# M1705Beco.net
KiCad netlist of a schematic drawn in EAGLE
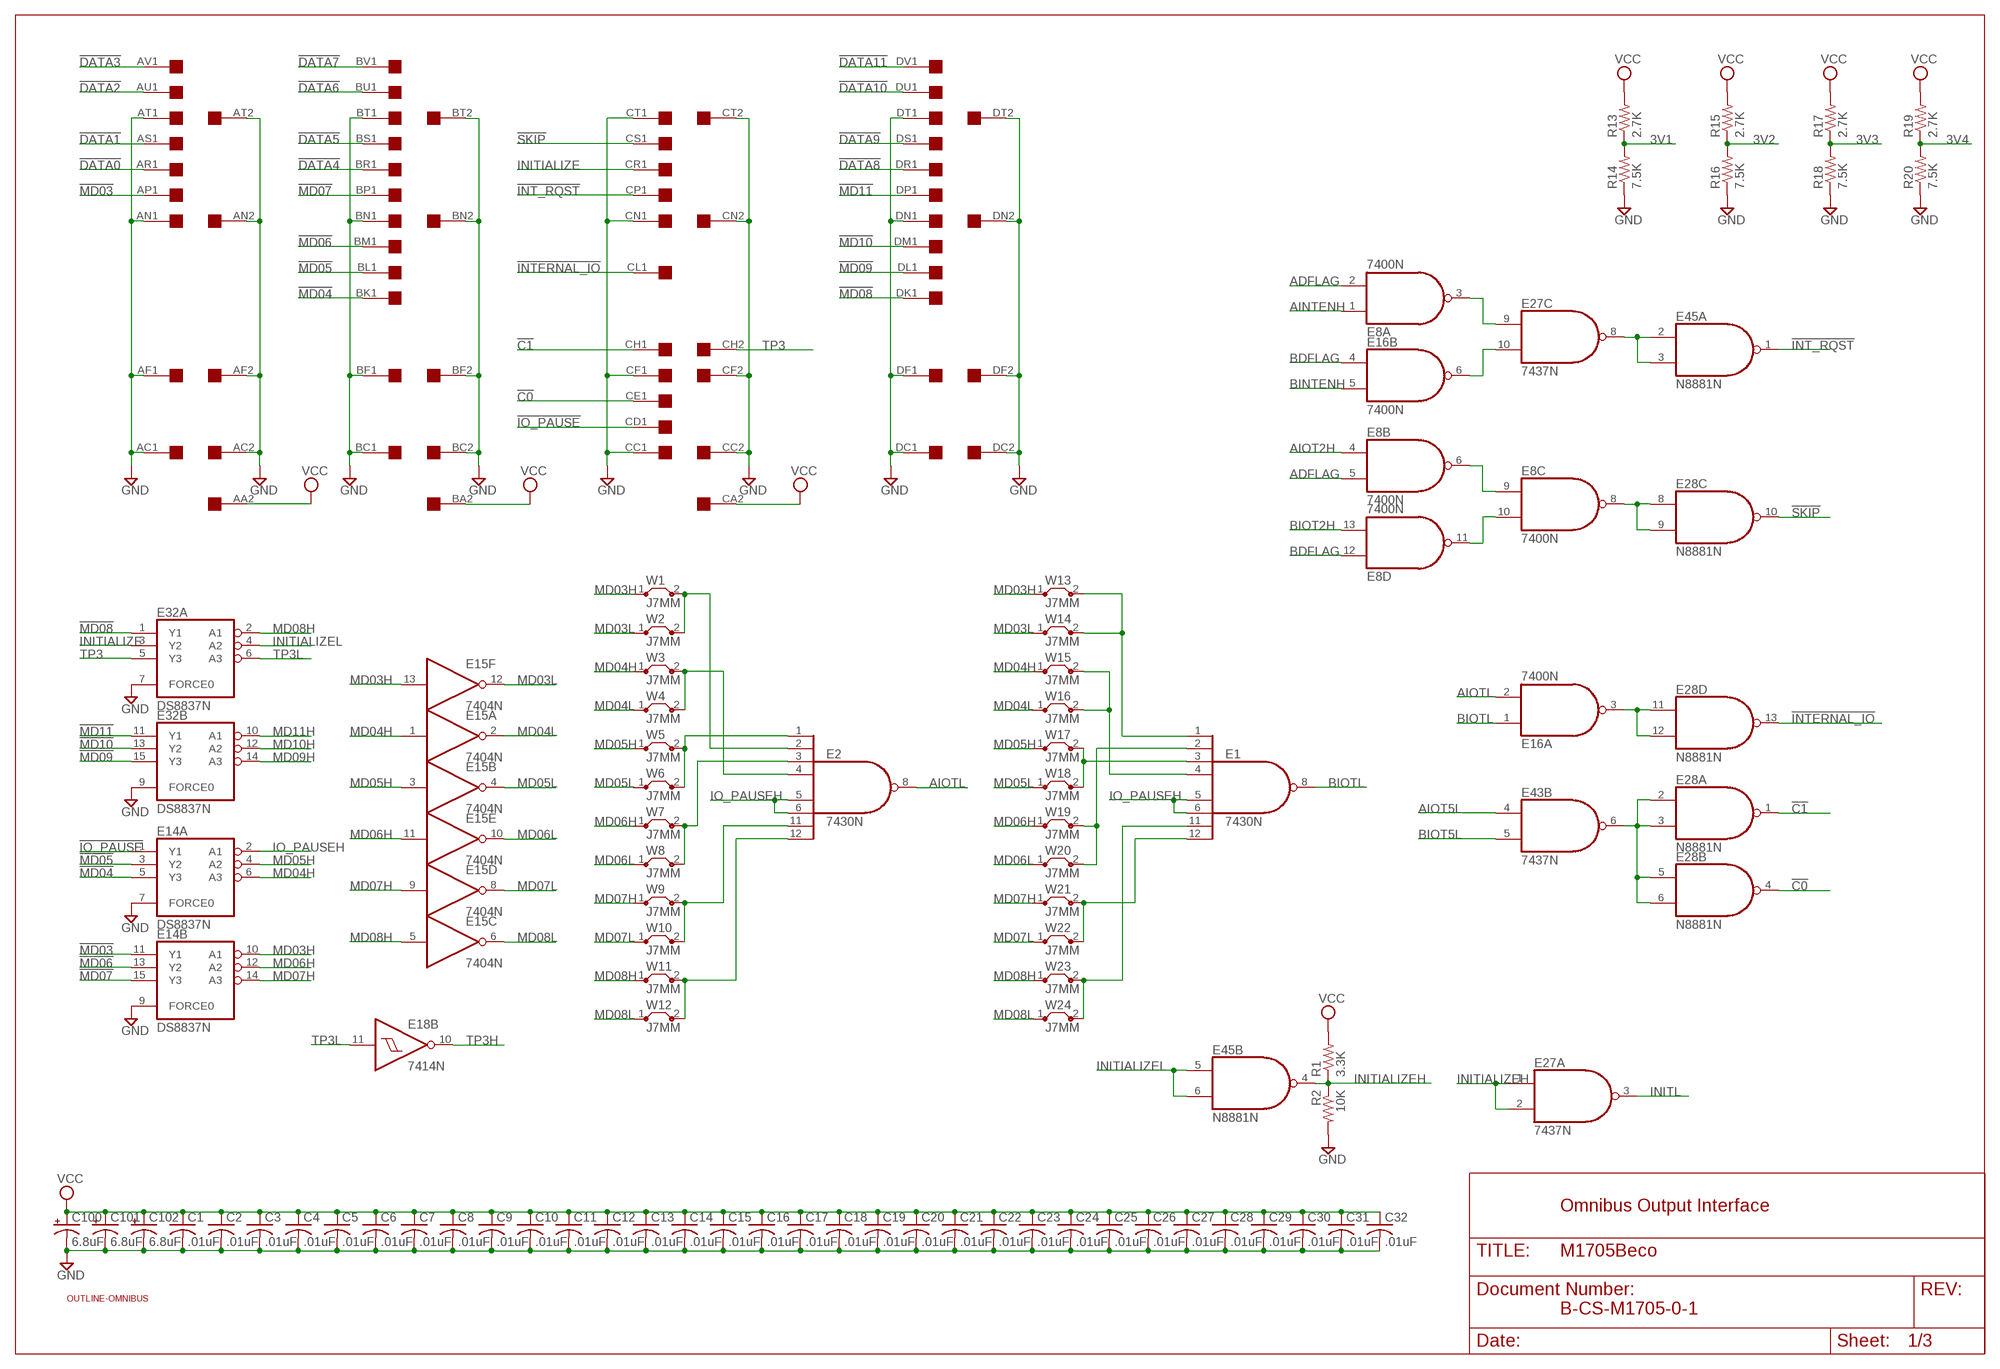
[diagram p0: schematic, sheet 1]
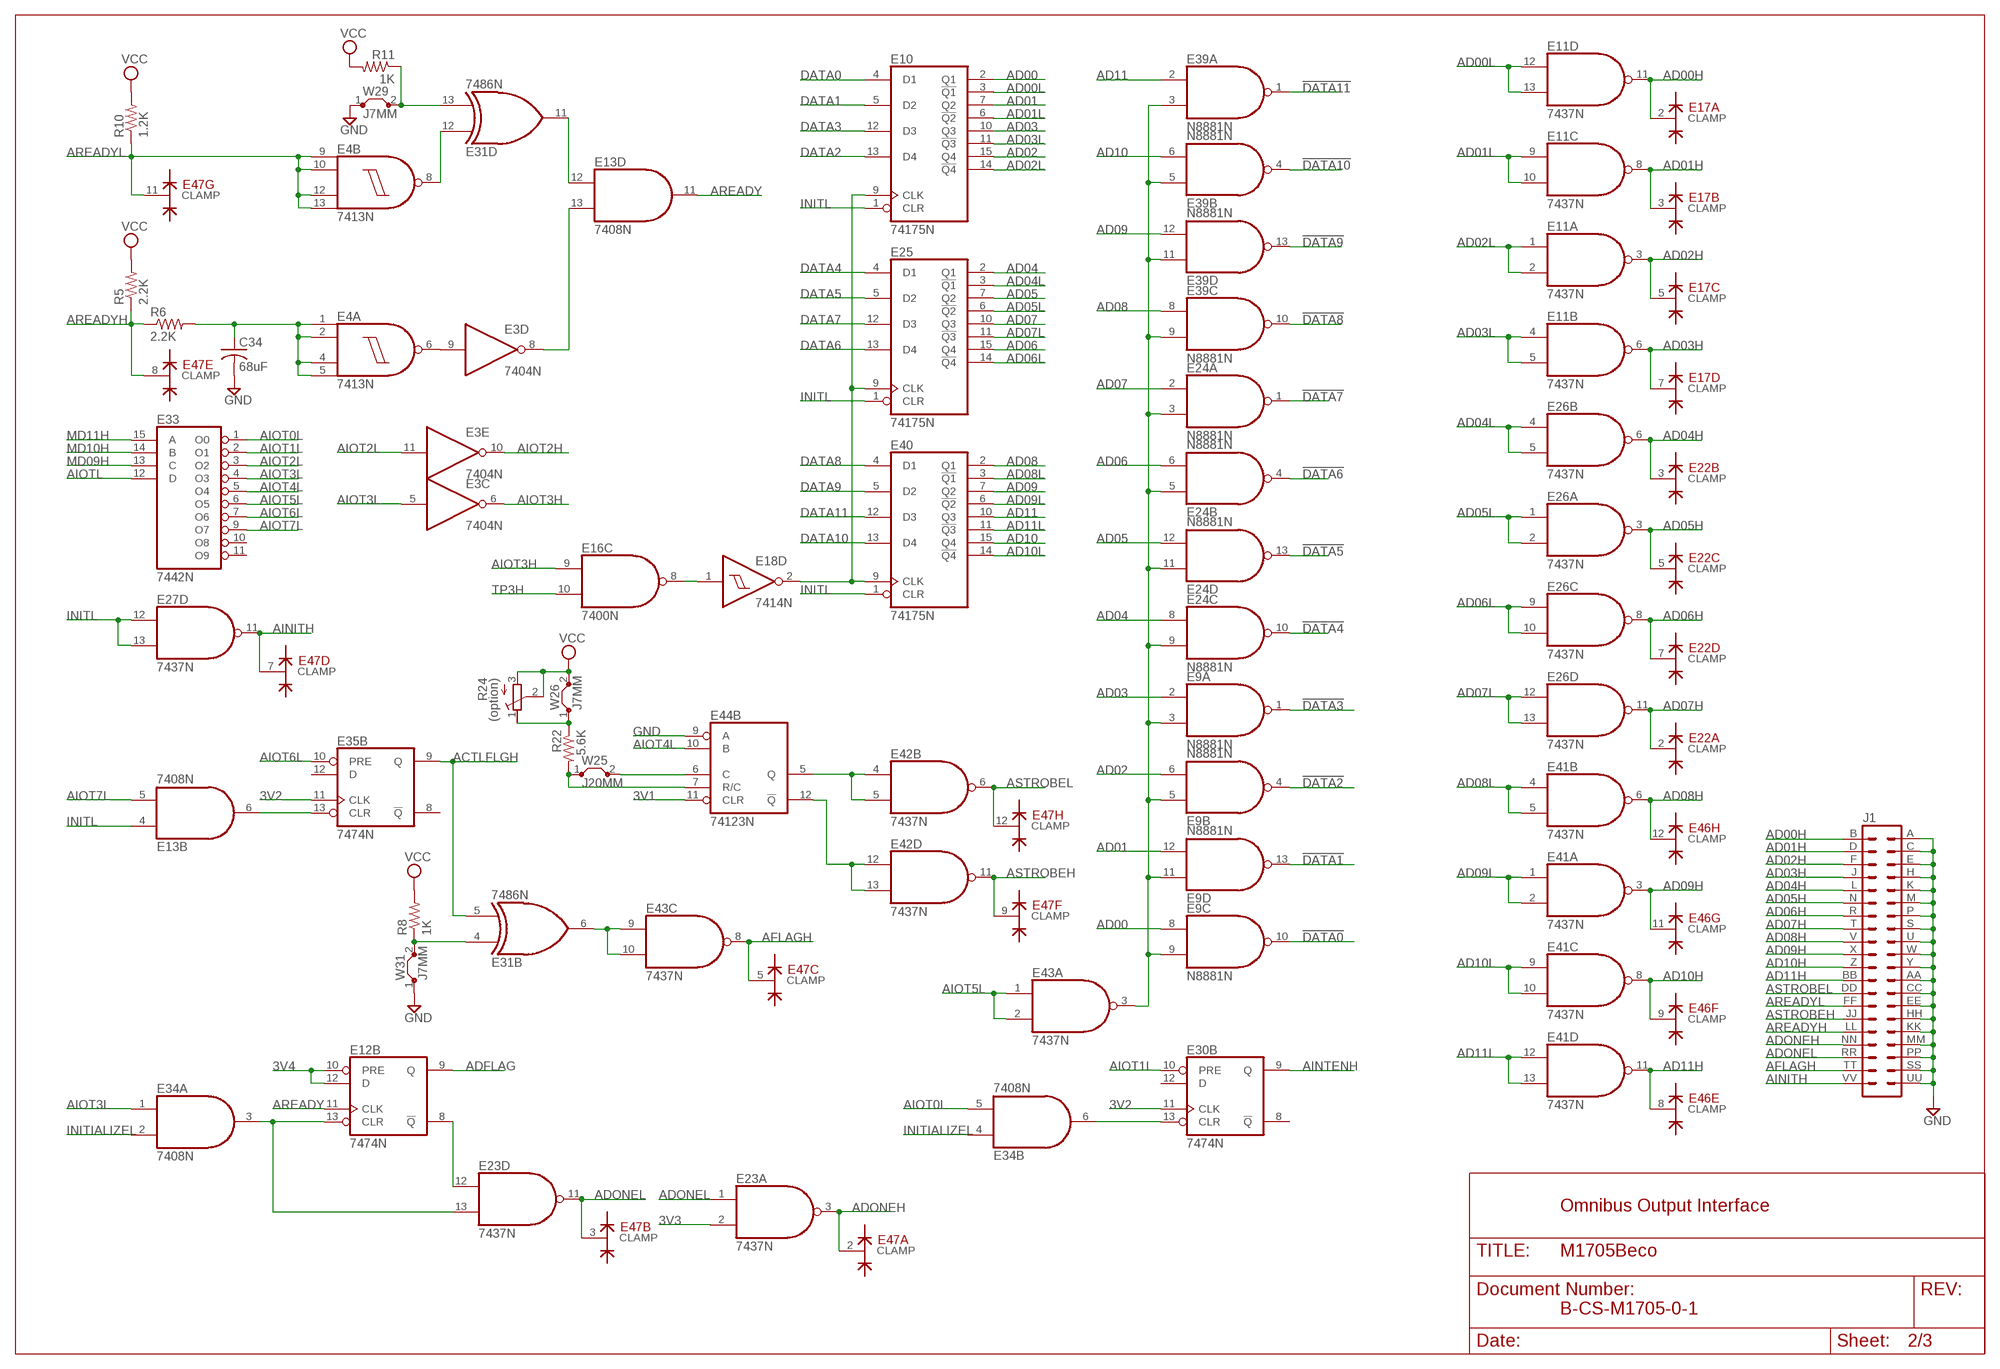
[diagram p1: schematic, sheet 2]
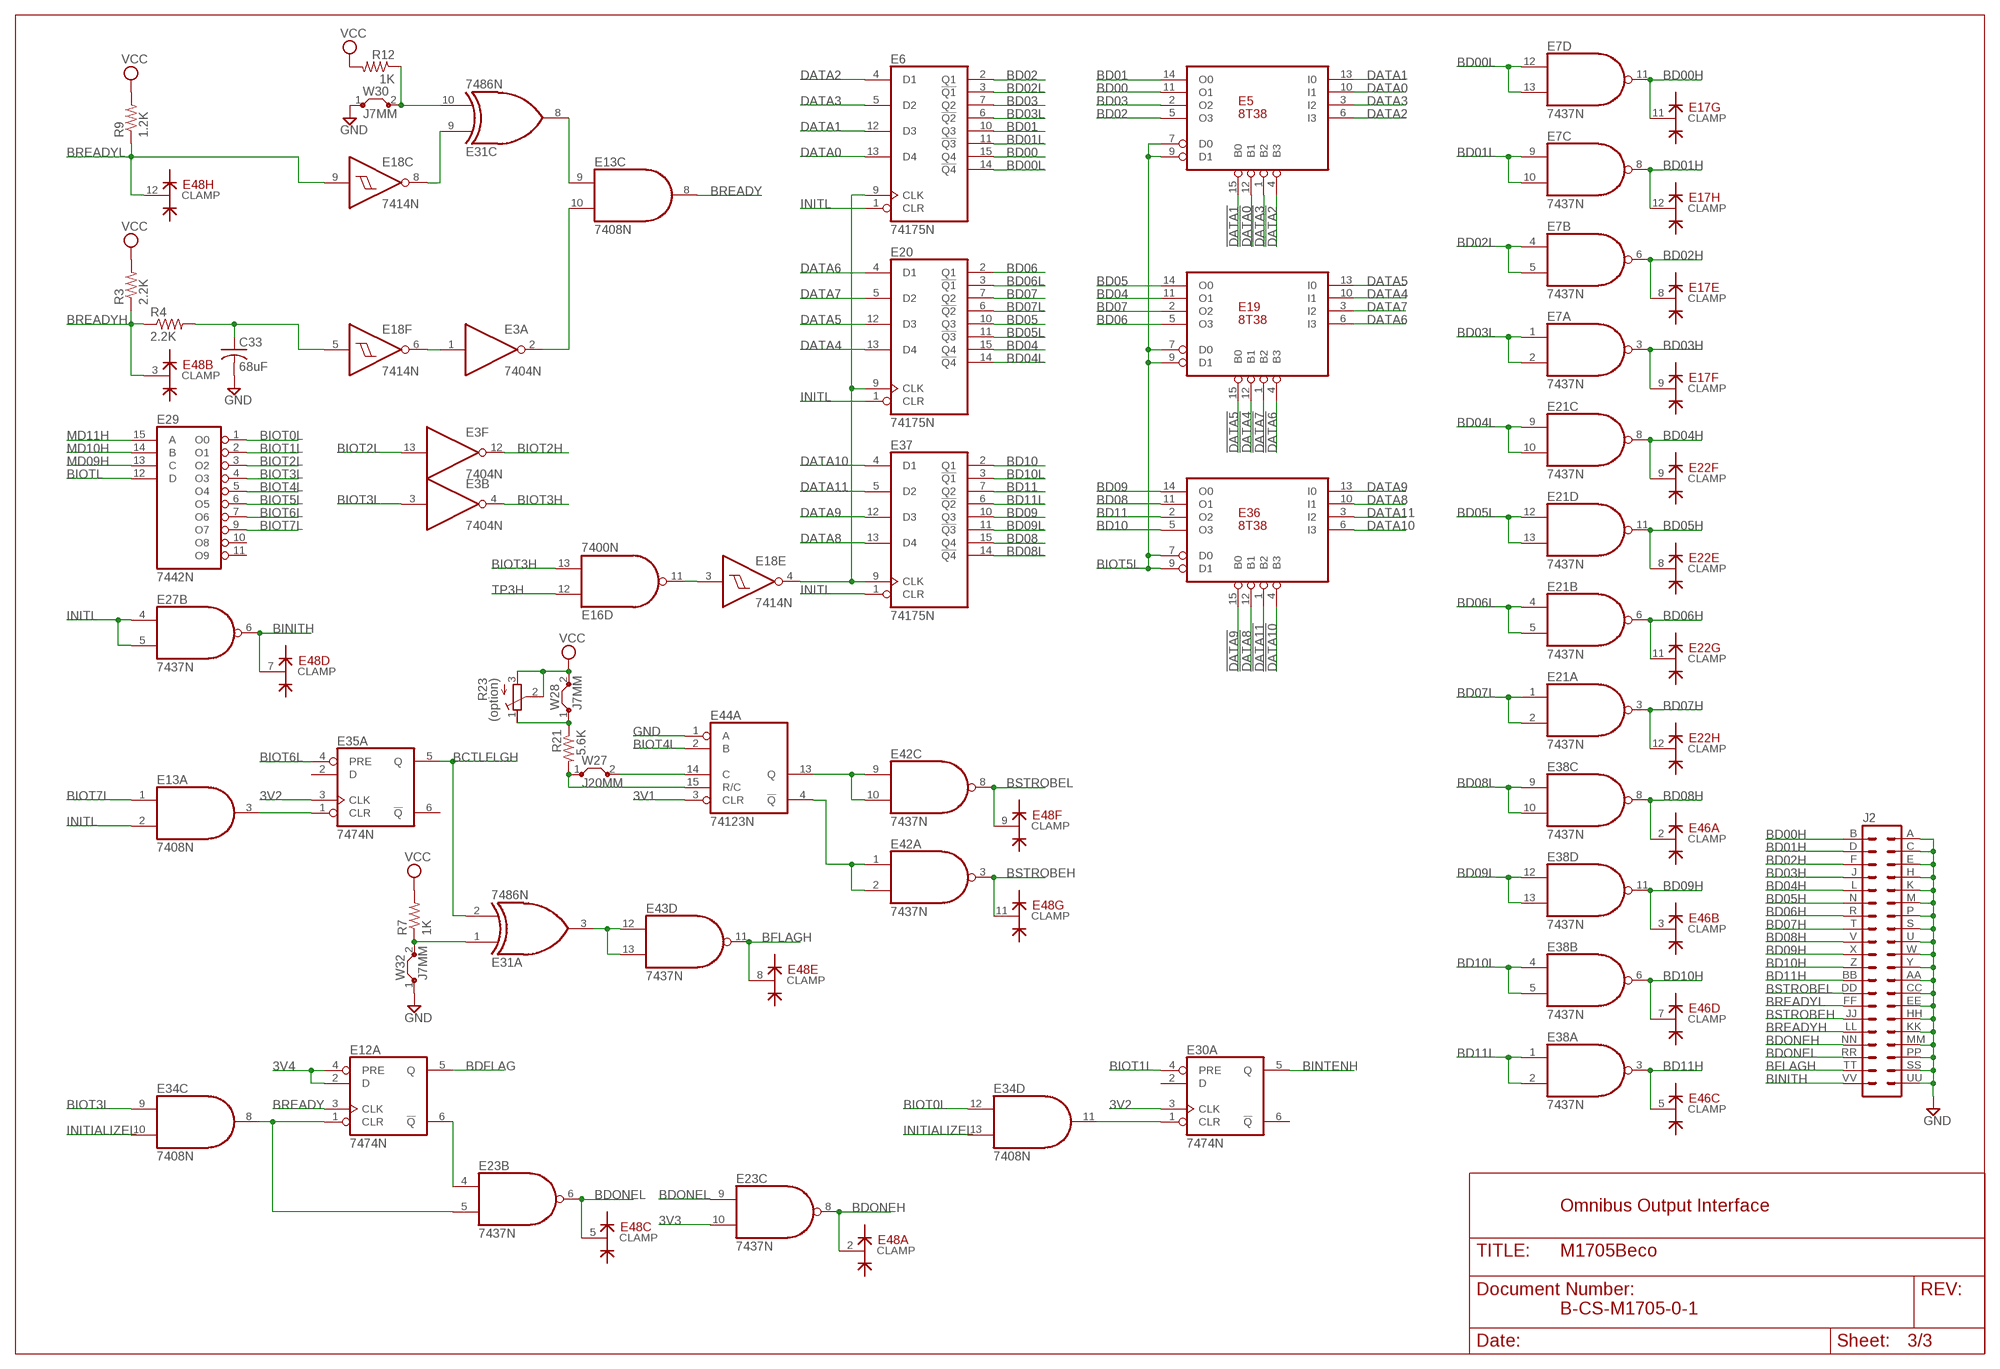
[diagram p2: schematic, sheet 3]

(export (version "E")
  (design (tool "Eeschema 10.0.6"))
  (components
    (comp (ref "C33")
      (value "68uF")
      (footprint "eagle-import:C102-043X133")
      (libsource (lib "eagle-import") (part "C-US102-043X133"))
    )
    (comp (ref "E3")
      (value "7404N")
      (footprint "eagle-import:DIL14")
      (libsource (lib "eagle-import") (part "7404N"))
    )
    (comp (ref "E5")
      (value "8T38")
      (footprint "eagle-import:DIL16")
      (libsource (lib "eagle-import") (part "DS8641N"))
    )
    (comp (ref "E6")
      (value "74175N")
      (footprint "eagle-import:DIL16")
      (libsource (lib "eagle-import") (part "74175N"))
    )
    (comp (ref "E7")
      (value "7437N")
      (footprint "eagle-import:DIL14")
      (libsource (lib "eagle-import") (part "7437N"))
    )
    (comp (ref "E12")
      (value "7474N")
      (footprint "eagle-import:DIL14")
      (libsource (lib "eagle-import") (part "7474NS"))
    )
    (comp (ref "E13")
      (value "7408N")
      (footprint "eagle-import:DIL14")
      (libsource (lib "eagle-import") (part "7408NLS"))
    )
    (comp (ref "E16")
      (value "7400N")
      (footprint "eagle-import:DIL14")
      (libsource (lib "eagle-import") (part "7400N"))
    )
    (comp (ref "E17")
      (value "DEC2501")
      (footprint "eagle-import:DIL14")
      (libsource (lib "eagle-import") (part "DEC2501"))
    )
    (comp (ref "E18")
      (value "7414N")
      (footprint "eagle-import:DIL14")
      (libsource (lib "eagle-import") (part "7414N"))
    )
    (comp (ref "E19")
      (value "8T38")
      (footprint "eagle-import:DIL16")
      (libsource (lib "eagle-import") (part "DS8641N"))
    )
    (comp (ref "E20")
      (value "74175N")
      (footprint "eagle-import:DIL16")
      (libsource (lib "eagle-import") (part "74175N"))
    )
    (comp (ref "E21")
      (value "7437N")
      (footprint "eagle-import:DIL14")
      (libsource (lib "eagle-import") (part "7437N"))
    )
    (comp (ref "E22")
      (value "DEC2501")
      (footprint "eagle-import:DIL14")
      (libsource (lib "eagle-import") (part "DEC2501"))
    )
    (comp (ref "E23")
      (value "7437N")
      (footprint "eagle-import:DIL14")
      (libsource (lib "eagle-import") (part "7437N"))
    )
    (comp (ref "E27")
      (value "7437N")
      (footprint "eagle-import:DIL14")
      (libsource (lib "eagle-import") (part "7437N"))
    )
    (comp (ref "E29")
      (value "7442N")
      (footprint "eagle-import:DIL16")
      (libsource (lib "eagle-import") (part "7442NLS"))
    )
    (comp (ref "E30")
      (value "7474N")
      (footprint "eagle-import:DIL14")
      (libsource (lib "eagle-import") (part "7474NS"))
    )
    (comp (ref "E31")
      (value "7486N")
      (footprint "eagle-import:DIL14")
      (libsource (lib "eagle-import") (part "7486N"))
    )
    (comp (ref "E34")
      (value "7408N")
      (footprint "eagle-import:DIL14")
      (libsource (lib "eagle-import") (part "7408NLS"))
    )
    (comp (ref "E35")
      (value "7474N")
      (footprint "eagle-import:DIL14")
      (libsource (lib "eagle-import") (part "7474NS"))
    )
    (comp (ref "E36")
      (value "8T38")
      (footprint "eagle-import:DIL16")
      (libsource (lib "eagle-import") (part "DS8641N"))
    )
    (comp (ref "E37")
      (value "74175N")
      (footprint "eagle-import:DIL16")
      (libsource (lib "eagle-import") (part "74175N"))
    )
    (comp (ref "E38")
      (value "7437N")
      (footprint "eagle-import:DIL14")
      (libsource (lib "eagle-import") (part "7437N"))
    )
    (comp (ref "E42")
      (value "7437N")
      (footprint "eagle-import:DIL14")
      (libsource (lib "eagle-import") (part "7437N"))
    )
    (comp (ref "E43")
      (value "7437N")
      (footprint "eagle-import:DIL14")
      (libsource (lib "eagle-import") (part "7437N"))
    )
    (comp (ref "E44")
      (value "74123N")
      (footprint "eagle-import:DIL16")
      (libsource (lib "eagle-import") (part "74123N"))
    )
    (comp (ref "E46")
      (value "DEC2501")
      (footprint "eagle-import:DIL14")
      (libsource (lib "eagle-import") (part "DEC2501"))
    )
    (comp (ref "E48")
      (value "DEC2501")
      (footprint "eagle-import:DIL14")
      (libsource (lib "eagle-import") (part "DEC2501"))
    )
    (comp (ref "J2")
      (value "DEC40PINH")
      (footprint "eagle-import:DEC40PINH")
      (libsource (lib "eagle-import") (part "DEC40PINH"))
    )
    (comp (ref "R3")
      (value "2.2K")
      (footprint "eagle-import:0207_10")
      (libsource (lib "eagle-import") (part "R-US_0207/10"))
    )
    (comp (ref "R4")
      (value "2.2K")
      (footprint "eagle-import:0207_10")
      (libsource (lib "eagle-import") (part "R-US_0207/10"))
    )
    (comp (ref "R7")
      (value "1K")
      (footprint "eagle-import:0207_10")
      (libsource (lib "eagle-import") (part "R-US_0207/10"))
    )
    (comp (ref "R9")
      (value "1.2K")
      (footprint "eagle-import:0207_10")
      (libsource (lib "eagle-import") (part "R-US_0207/10"))
    )
    (comp (ref "R12")
      (value "1K")
      (footprint "eagle-import:0207_10")
      (libsource (lib "eagle-import") (part "R-US_0207/10"))
    )
    (comp (ref "R21")
      (value "5.6K")
      (footprint "eagle-import:0207_10")
      (libsource (lib "eagle-import") (part "R-US_0207/10"))
    )
    (comp (ref "R23")
      (value "(option)")
      (footprint "eagle-import:3006Y")
      (libsource (lib "eagle-import") (part "275P"))
    )
    (comp (ref "W27")
      (value "J20MM")
      (footprint "eagle-import:20")
      (libsource (lib "eagle-import") (part "J20MM"))
    )
    (comp (ref "W28")
      (value "J7MM")
      (footprint "eagle-import:07")
      (libsource (lib "eagle-import") (part "J7MM"))
    )
    (comp (ref "W30")
      (value "J7MM")
      (footprint "eagle-import:07")
      (libsource (lib "eagle-import") (part "J7MM"))
    )
    (comp (ref "W32")
      (value "J7MM")
      (footprint "eagle-import:07")
      (libsource (lib "eagle-import") (part "J7MM"))
    )
    (comp (ref "C1")
      (value ".01uF")
      (footprint "eagle-import:C075-032X103")
      (libsource (lib "eagle-import") (part "C-US075-032X103"))
    )
    (comp (ref "C2")
      (value ".01uF")
      (footprint "eagle-import:C075-032X103")
      (libsource (lib "eagle-import") (part "C-US075-032X103"))
    )
    (comp (ref "C3")
      (value ".01uF")
      (footprint "eagle-import:C075-032X103")
      (libsource (lib "eagle-import") (part "C-US075-032X103"))
    )
    (comp (ref "C4")
      (value ".01uF")
      (footprint "eagle-import:C075-032X103")
      (libsource (lib "eagle-import") (part "C-US075-032X103"))
    )
    (comp (ref "C5")
      (value ".01uF")
      (footprint "eagle-import:C075-032X103")
      (libsource (lib "eagle-import") (part "C-US075-032X103"))
    )
    (comp (ref "C6")
      (value ".01uF")
      (footprint "eagle-import:C075-032X103")
      (libsource (lib "eagle-import") (part "C-US075-032X103"))
    )
    (comp (ref "C7")
      (value ".01uF")
      (footprint "eagle-import:C075-032X103")
      (libsource (lib "eagle-import") (part "C-US075-032X103"))
    )
    (comp (ref "C8")
      (value ".01uF")
      (footprint "eagle-import:C075-032X103")
      (libsource (lib "eagle-import") (part "C-US075-032X103"))
    )
    (comp (ref "C9")
      (value ".01uF")
      (footprint "eagle-import:C075-032X103")
      (libsource (lib "eagle-import") (part "C-US075-032X103"))
    )
    (comp (ref "C10")
      (value ".01uF")
      (footprint "eagle-import:C075-032X103")
      (libsource (lib "eagle-import") (part "C-US075-032X103"))
    )
    (comp (ref "C11")
      (value ".01uF")
      (footprint "eagle-import:C075-032X103")
      (libsource (lib "eagle-import") (part "C-US075-032X103"))
    )
    (comp (ref "C12")
      (value ".01uF")
      (footprint "eagle-import:C075-032X103")
      (libsource (lib "eagle-import") (part "C-US075-032X103"))
    )
    (comp (ref "C13")
      (value ".01uF")
      (footprint "eagle-import:C075-032X103")
      (libsource (lib "eagle-import") (part "C-US075-032X103"))
    )
    (comp (ref "C14")
      (value ".01uF")
      (footprint "eagle-import:C075-032X103")
      (libsource (lib "eagle-import") (part "C-US075-032X103"))
    )
    (comp (ref "C15")
      (value ".01uF")
      (footprint "eagle-import:C075-032X103")
      (libsource (lib "eagle-import") (part "C-US075-032X103"))
    )
    (comp (ref "C16")
      (value ".01uF")
      (footprint "eagle-import:C075-032X103")
      (libsource (lib "eagle-import") (part "C-US075-032X103"))
    )
    (comp (ref "C17")
      (value ".01uF")
      (footprint "eagle-import:C075-032X103")
      (libsource (lib "eagle-import") (part "C-US075-032X103"))
    )
    (comp (ref "C18")
      (value ".01uF")
      (footprint "eagle-import:C075-032X103")
      (libsource (lib "eagle-import") (part "C-US075-032X103"))
    )
    (comp (ref "C19")
      (value ".01uF")
      (footprint "eagle-import:C075-032X103")
      (libsource (lib "eagle-import") (part "C-US075-032X103"))
    )
    (comp (ref "C20")
      (value ".01uF")
      (footprint "eagle-import:C075-032X103")
      (libsource (lib "eagle-import") (part "C-US075-032X103"))
    )
    (comp (ref "C21")
      (value ".01uF")
      (footprint "eagle-import:C075-032X103")
      (libsource (lib "eagle-import") (part "C-US075-032X103"))
    )
    (comp (ref "C22")
      (value ".01uF")
      (footprint "eagle-import:C075-032X103")
      (libsource (lib "eagle-import") (part "C-US075-032X103"))
    )
    (comp (ref "C23")
      (value ".01uF")
      (footprint "eagle-import:C075-032X103")
      (libsource (lib "eagle-import") (part "C-US075-032X103"))
    )
    (comp (ref "C24")
      (value ".01uF")
      (footprint "eagle-import:C075-032X103")
      (libsource (lib "eagle-import") (part "C-US075-032X103"))
    )
    (comp (ref "C25")
      (value ".01uF")
      (footprint "eagle-import:C075-032X103")
      (libsource (lib "eagle-import") (part "C-US075-032X103"))
    )
    (comp (ref "C26")
      (value ".01uF")
      (footprint "eagle-import:C075-032X103")
      (libsource (lib "eagle-import") (part "C-US075-032X103"))
    )
    (comp (ref "C27")
      (value ".01uF")
      (footprint "eagle-import:C075-032X103")
      (libsource (lib "eagle-import") (part "C-US075-032X103"))
    )
    (comp (ref "C28")
      (value ".01uF")
      (footprint "eagle-import:C075-032X103")
      (libsource (lib "eagle-import") (part "C-US075-032X103"))
    )
    (comp (ref "C29")
      (value ".01uF")
      (footprint "eagle-import:C075-032X103")
      (libsource (lib "eagle-import") (part "C-US075-032X103"))
    )
    (comp (ref "C30")
      (value ".01uF")
      (footprint "eagle-import:C075-032X103")
      (libsource (lib "eagle-import") (part "C-US075-032X103"))
    )
    (comp (ref "C31")
      (value ".01uF")
      (footprint "eagle-import:C075-032X103")
      (libsource (lib "eagle-import") (part "C-US075-032X103"))
    )
    (comp (ref "C32")
      (value ".01uF")
      (footprint "eagle-import:C075-032X103")
      (libsource (lib "eagle-import") (part "C-US075-032X103"))
    )
    (comp (ref "C100")
      (value "6.8uF")
      (footprint "eagle-import:E12-8")
      (libsource (lib "eagle-import") (part "CPOL-USE20-8AXIAL"))
    )
    (comp (ref "C101")
      (value "6.8uF")
      (footprint "eagle-import:E12-8")
      (libsource (lib "eagle-import") (part "CPOL-USE20-8AXIAL"))
    )
    (comp (ref "C102")
      (value "6.8uF")
      (footprint "eagle-import:E12-8")
      (libsource (lib "eagle-import") (part "CPOL-USE20-8AXIAL"))
    )
    (comp (ref "E1")
      (value "7430N")
      (footprint "eagle-import:DIL14")
      (libsource (lib "eagle-import") (part "7430N"))
    )
    (comp (ref "E2")
      (value "7430N")
      (footprint "eagle-import:DIL14")
      (libsource (lib "eagle-import") (part "7430N"))
    )
    (comp (ref "E8")
      (value "7400N")
      (footprint "eagle-import:DIL14")
      (libsource (lib "eagle-import") (part "7400N"))
    )
    (comp (ref "E14")
      (value "DS8837N")
      (footprint "eagle-import:DIL16")
      (libsource (lib "eagle-import") (part "DS8837N"))
    )
    (comp (ref "E15")
      (value "7404N")
      (footprint "eagle-import:DIL14")
      (libsource (lib "eagle-import") (part "7404N"))
    )
    (comp (ref "E28")
      (value "N8881N")
      (footprint "eagle-import:DIL14")
      (libsource (lib "eagle-import") (part "N8881N"))
    )
    (comp (ref "E32")
      (value "DS8837N")
      (footprint "eagle-import:DIL16")
      (libsource (lib "eagle-import") (part "DS8837N"))
    )
    (comp (ref "E45")
      (value "N8881N")
      (footprint "eagle-import:DIL14")
      (libsource (lib "eagle-import") (part "N8881N"))
    )
    (comp (ref "R1")
      (value "3.3K")
      (footprint "eagle-import:0207_10")
      (libsource (lib "eagle-import") (part "R-US_0207/10"))
    )
    (comp (ref "R2")
      (value "10K")
      (footprint "eagle-import:0207_10")
      (libsource (lib "eagle-import") (part "R-US_0207/10"))
    )
    (comp (ref "R13")
      (value "2.7K")
      (footprint "eagle-import:0207_10")
      (libsource (lib "eagle-import") (part "R-US_0207/10"))
    )
    (comp (ref "R14")
      (value "7.5K")
      (footprint "eagle-import:0207_10")
      (libsource (lib "eagle-import") (part "R-US_0207/10"))
    )
    (comp (ref "R15")
      (value "2.7K")
      (footprint "eagle-import:0207_10")
      (libsource (lib "eagle-import") (part "R-US_0207/10"))
    )
    (comp (ref "R16")
      (value "7.5K")
      (footprint "eagle-import:0207_10")
      (libsource (lib "eagle-import") (part "R-US_0207/10"))
    )
    (comp (ref "R17")
      (value "2.7K")
      (footprint "eagle-import:0207_10")
      (libsource (lib "eagle-import") (part "R-US_0207/10"))
    )
    (comp (ref "R18")
      (value "7.5K")
      (footprint "eagle-import:0207_10")
      (libsource (lib "eagle-import") (part "R-US_0207/10"))
    )
    (comp (ref "R19")
      (value "2.7K")
      (footprint "eagle-import:0207_10")
      (libsource (lib "eagle-import") (part "R-US_0207/10"))
    )
    (comp (ref "R20")
      (value "7.5K")
      (footprint "eagle-import:0207_10")
      (libsource (lib "eagle-import") (part "R-US_0207/10"))
    )
    (comp (ref "U$2")
      (value "QUAD")
      (footprint "eagle-import:EDGE-CON8")
      (libsource (lib "eagle-import") (part "QUAD"))
    )
    (comp (ref "U$4")
      (value "OUTLINE-OMNIBUS")
      (footprint "eagle-import:OMNIBUS")
      (libsource (lib "eagle-import") (part "OUTLINE-OMNIBUS"))
    )
    (comp (ref "W1")
      (value "J7MM")
      (footprint "eagle-import:07")
      (libsource (lib "eagle-import") (part "J7MM"))
    )
    (comp (ref "W2")
      (value "J7MM")
      (footprint "eagle-import:07")
      (libsource (lib "eagle-import") (part "J7MM"))
    )
    (comp (ref "W3")
      (value "J7MM")
      (footprint "eagle-import:07")
      (libsource (lib "eagle-import") (part "J7MM"))
    )
    (comp (ref "W4")
      (value "J7MM")
      (footprint "eagle-import:07")
      (libsource (lib "eagle-import") (part "J7MM"))
    )
    (comp (ref "W5")
      (value "J7MM")
      (footprint "eagle-import:07")
      (libsource (lib "eagle-import") (part "J7MM"))
    )
    (comp (ref "W6")
      (value "J7MM")
      (footprint "eagle-import:07")
      (libsource (lib "eagle-import") (part "J7MM"))
    )
    (comp (ref "W7")
      (value "J7MM")
      (footprint "eagle-import:07")
      (libsource (lib "eagle-import") (part "J7MM"))
    )
    (comp (ref "W8")
      (value "J7MM")
      (footprint "eagle-import:07")
      (libsource (lib "eagle-import") (part "J7MM"))
    )
    (comp (ref "W9")
      (value "J7MM")
      (footprint "eagle-import:07")
      (libsource (lib "eagle-import") (part "J7MM"))
    )
    (comp (ref "W10")
      (value "J7MM")
      (footprint "eagle-import:07")
      (libsource (lib "eagle-import") (part "J7MM"))
    )
    (comp (ref "W11")
      (value "J7MM")
      (footprint "eagle-import:07")
      (libsource (lib "eagle-import") (part "J7MM"))
    )
    (comp (ref "W12")
      (value "J7MM")
      (footprint "eagle-import:07")
      (libsource (lib "eagle-import") (part "J7MM"))
    )
    (comp (ref "W13")
      (value "J7MM")
      (footprint "eagle-import:07")
      (libsource (lib "eagle-import") (part "J7MM"))
    )
    (comp (ref "W14")
      (value "J7MM")
      (footprint "eagle-import:07")
      (libsource (lib "eagle-import") (part "J7MM"))
    )
    (comp (ref "W15")
      (value "J7MM")
      (footprint "eagle-import:07")
      (libsource (lib "eagle-import") (part "J7MM"))
    )
    (comp (ref "W16")
      (value "J7MM")
      (footprint "eagle-import:07")
      (libsource (lib "eagle-import") (part "J7MM"))
    )
    (comp (ref "W17")
      (value "J7MM")
      (footprint "eagle-import:07")
      (libsource (lib "eagle-import") (part "J7MM"))
    )
    (comp (ref "W18")
      (value "J7MM")
      (footprint "eagle-import:07")
      (libsource (lib "eagle-import") (part "J7MM"))
    )
    (comp (ref "W19")
      (value "J7MM")
      (footprint "eagle-import:07")
      (libsource (lib "eagle-import") (part "J7MM"))
    )
    (comp (ref "W20")
      (value "J7MM")
      (footprint "eagle-import:07")
      (libsource (lib "eagle-import") (part "J7MM"))
    )
    (comp (ref "W21")
      (value "J7MM")
      (footprint "eagle-import:07")
      (libsource (lib "eagle-import") (part "J7MM"))
    )
    (comp (ref "W22")
      (value "J7MM")
      (footprint "eagle-import:07")
      (libsource (lib "eagle-import") (part "J7MM"))
    )
    (comp (ref "W23")
      (value "J7MM")
      (footprint "eagle-import:07")
      (libsource (lib "eagle-import") (part "J7MM"))
    )
    (comp (ref "W24")
      (value "J7MM")
      (footprint "eagle-import:07")
      (libsource (lib "eagle-import") (part "J7MM"))
    )
    (comp (ref "C34")
      (value "68uF")
      (footprint "eagle-import:C102-043X133")
      (libsource (lib "eagle-import") (part "C-US102-043X133"))
    )
    (comp (ref "E4")
      (value "7413N")
      (footprint "eagle-import:DIL14")
      (libsource (lib "eagle-import") (part "7413N"))
    )
    (comp (ref "E9")
      (value "N8881N")
      (footprint "eagle-import:DIL14")
      (libsource (lib "eagle-import") (part "N8881N"))
    )
    (comp (ref "E10")
      (value "74175N")
      (footprint "eagle-import:DIL16")
      (libsource (lib "eagle-import") (part "74175N"))
    )
    (comp (ref "E11")
      (value "7437N")
      (footprint "eagle-import:DIL14")
      (libsource (lib "eagle-import") (part "7437N"))
    )
    (comp (ref "E24")
      (value "N8881N")
      (footprint "eagle-import:DIL14")
      (libsource (lib "eagle-import") (part "N8881N"))
    )
    (comp (ref "E25")
      (value "74175N")
      (footprint "eagle-import:DIL16")
      (libsource (lib "eagle-import") (part "74175N"))
    )
    (comp (ref "E26")
      (value "7437N")
      (footprint "eagle-import:DIL14")
      (libsource (lib "eagle-import") (part "7437N"))
    )
    (comp (ref "E33")
      (value "7442N")
      (footprint "eagle-import:DIL16")
      (libsource (lib "eagle-import") (part "7442NLS"))
    )
    (comp (ref "E39")
      (value "N8881N")
      (footprint "eagle-import:DIL14")
      (libsource (lib "eagle-import") (part "N8881N"))
    )
    (comp (ref "E40")
      (value "74175N")
      (footprint "eagle-import:DIL16")
      (libsource (lib "eagle-import") (part "74175N"))
    )
    (comp (ref "E41")
      (value "7437N")
      (footprint "eagle-import:DIL14")
      (libsource (lib "eagle-import") (part "7437N"))
    )
    (comp (ref "E47")
      (value "DEC2501")
      (footprint "eagle-import:DIL14")
      (libsource (lib "eagle-import") (part "DEC2501"))
    )
    (comp (ref "J1")
      (value "DEC40PINH")
      (footprint "eagle-import:DEC40PINH")
      (libsource (lib "eagle-import") (part "DEC40PINH"))
    )
    (comp (ref "R5")
      (value "2.2K")
      (footprint "eagle-import:0207_10")
      (libsource (lib "eagle-import") (part "R-US_0207/10"))
    )
    (comp (ref "R6")
      (value "2.2K")
      (footprint "eagle-import:0207_10")
      (libsource (lib "eagle-import") (part "R-US_0207/10"))
    )
    (comp (ref "R8")
      (value "1K")
      (footprint "eagle-import:0207_10")
      (libsource (lib "eagle-import") (part "R-US_0207/10"))
    )
    (comp (ref "R10")
      (value "1.2K")
      (footprint "eagle-import:0207_10")
      (libsource (lib "eagle-import") (part "R-US_0207/10"))
    )
    (comp (ref "R11")
      (value "1K")
      (footprint "eagle-import:0207_10")
      (libsource (lib "eagle-import") (part "R-US_0207/10"))
    )
    (comp (ref "R22")
      (value "5.6K")
      (footprint "eagle-import:0207_10")
      (libsource (lib "eagle-import") (part "R-US_0207/10"))
    )
    (comp (ref "R24")
      (value "(option)")
      (footprint "eagle-import:3006Y")
      (libsource (lib "eagle-import") (part "275P"))
    )
    (comp (ref "W25")
      (value "J20MM")
      (footprint "eagle-import:20")
      (libsource (lib "eagle-import") (part "J20MM"))
    )
    (comp (ref "W26")
      (value "J7MM")
      (footprint "eagle-import:07")
      (libsource (lib "eagle-import") (part "J7MM"))
    )
    (comp (ref "W29")
      (value "J7MM")
      (footprint "eagle-import:07")
      (libsource (lib "eagle-import") (part "J7MM"))
    )
    (comp (ref "W31")
      (value "J7MM")
      (footprint "eagle-import:07")
      (libsource (lib "eagle-import") (part "J7MM"))
    )
  )
  (nets
    (net (code "1") (name "3V1") (class "Default")
      (node (ref "E44") (pin "11") (pinfunction "CLR_11") (pintype "input"))
      (node (ref "E44") (pin "3") (pinfunction "CLR_3") (pintype "input"))
      (node (ref "R13") (pin "1") (pinfunction "1_1") (pintype "passive"))
      (node (ref "R14") (pin "2") (pinfunction "2_2") (pintype "passive"))
    )
    (net (code "2") (name "3V2") (class "Default")
      (node (ref "E30") (pin "11") (pinfunction "CLK_11") (pintype "input"))
      (node (ref "E30") (pin "3") (pinfunction "CLK_3") (pintype "input"))
      (node (ref "E35") (pin "11") (pinfunction "CLK_11") (pintype "input"))
      (node (ref "E35") (pin "3") (pinfunction "CLK_3") (pintype "input"))
      (node (ref "R15") (pin "1") (pinfunction "1_1") (pintype "passive"))
      (node (ref "R16") (pin "2") (pinfunction "2_2") (pintype "passive"))
    )
    (net (code "3") (name "3V3") (class "Default")
      (node (ref "E23") (pin "10") (pinfunction "I1_10") (pintype "input"))
      (node (ref "E23") (pin "2") (pinfunction "I1_2") (pintype "input"))
      (node (ref "R17") (pin "1") (pinfunction "1_1") (pintype "passive"))
      (node (ref "R18") (pin "2") (pinfunction "2_2") (pintype "passive"))
    )
    (net (code "4") (name "3V4") (class "Default")
      (node (ref "E12") (pin "10") (pinfunction "PRE_10") (pintype "input"))
      (node (ref "E12") (pin "12") (pinfunction "D_12") (pintype "input"))
      (node (ref "E12") (pin "2") (pinfunction "D_2") (pintype "input"))
      (node (ref "E12") (pin "4") (pinfunction "PRE_4") (pintype "input"))
      (node (ref "R19") (pin "1") (pinfunction "1_1") (pintype "passive"))
      (node (ref "R20") (pin "2") (pinfunction "2_2") (pintype "passive"))
    )
    (net (code "5") (name "ACTLFLGH") (class "Default")
      (node (ref "E31") (pin "5") (pinfunction "I1_5") (pintype "input"))
      (node (ref "E35") (pin "9") (pinfunction "Q_9") (pintype "output"))
    )
    (net (code "6") (name "AD00") (class "Default")
      (node (ref "E10") (pin "2") (pinfunction "Q1_2") (pintype "output"))
      (node (ref "E9") (pin "8") (pinfunction "I0_8") (pintype "input"))
    )
    (net (code "7") (name "AD00H") (class "Default")
      (node (ref "E11") (pin "11") (pinfunction "O_11") (pintype "output"))
      (node (ref "E17") (pin "2") (pinfunction "CLAMP_2") (pintype "input"))
      (node (ref "J1") (pin "B") (pinfunction "2_B") (pintype "bidirectional"))
    )
    (net (code "8") (name "AD00L") (class "Default")
      (node (ref "E10") (pin "3") (pinfunction "~{Q1}_3") (pintype "output"))
      (node (ref "E11") (pin "12") (pinfunction "I0_12") (pintype "input"))
      (node (ref "E11") (pin "13") (pinfunction "I1_13") (pintype "input"))
    )
    (net (code "9") (name "AD01") (class "Default")
      (node (ref "E10") (pin "7") (pinfunction "Q2_7") (pintype "output"))
      (node (ref "E9") (pin "12") (pinfunction "I1_12") (pintype "input"))
    )
    (net (code "10") (name "AD01H") (class "Default")
      (node (ref "E11") (pin "8") (pinfunction "O_8") (pintype "output"))
      (node (ref "E17") (pin "3") (pinfunction "CLAMP_3") (pintype "input"))
      (node (ref "J1") (pin "D") (pinfunction "4_D") (pintype "bidirectional"))
    )
    (net (code "11") (name "AD01L") (class "Default")
      (node (ref "E10") (pin "6") (pinfunction "~{Q2}_6") (pintype "output"))
      (node (ref "E11") (pin "10") (pinfunction "I1_10") (pintype "input"))
      (node (ref "E11") (pin "9") (pinfunction "I0_9") (pintype "input"))
    )
    (net (code "12") (name "AD02") (class "Default")
      (node (ref "E10") (pin "15") (pinfunction "Q4_15") (pintype "output"))
      (node (ref "E9") (pin "6") (pinfunction "I1_6") (pintype "input"))
    )
    (net (code "13") (name "AD02H") (class "Default")
      (node (ref "E11") (pin "3") (pinfunction "O_3") (pintype "output"))
      (node (ref "E17") (pin "5") (pinfunction "CLAMP_5") (pintype "input"))
      (node (ref "J1") (pin "F") (pinfunction "6_F") (pintype "bidirectional"))
    )
    (net (code "14") (name "AD02L") (class "Default")
      (node (ref "E10") (pin "14") (pinfunction "~{Q4}_14") (pintype "output"))
      (node (ref "E11") (pin "1") (pinfunction "I0_1") (pintype "input"))
      (node (ref "E11") (pin "2") (pinfunction "I1_2") (pintype "input"))
    )
    (net (code "15") (name "AD03") (class "Default")
      (node (ref "E10") (pin "10") (pinfunction "Q3_10") (pintype "output"))
      (node (ref "E9") (pin "2") (pinfunction "I0_2") (pintype "input"))
    )
    (net (code "16") (name "AD03H") (class "Default")
      (node (ref "E11") (pin "6") (pinfunction "O_6") (pintype "output"))
      (node (ref "E17") (pin "7") (pinfunction "CLAMP_7") (pintype "input"))
      (node (ref "J1") (pin "J") (pinfunction "8_J") (pintype "bidirectional"))
    )
    (net (code "17") (name "AD03L") (class "Default")
      (node (ref "E10") (pin "11") (pinfunction "~{Q3}_11") (pintype "output"))
      (node (ref "E11") (pin "4") (pinfunction "I0_4") (pintype "input"))
      (node (ref "E11") (pin "5") (pinfunction "I1_5") (pintype "input"))
    )
    (net (code "18") (name "AD04") (class "Default")
      (node (ref "E24") (pin "8") (pinfunction "I0_8") (pintype "input"))
      (node (ref "E25") (pin "2") (pinfunction "Q1_2") (pintype "output"))
    )
    (net (code "19") (name "AD04H") (class "Default")
      (node (ref "E22") (pin "3") (pinfunction "CLAMP_3") (pintype "input"))
      (node (ref "E26") (pin "6") (pinfunction "O_6") (pintype "output"))
      (node (ref "J1") (pin "L") (pinfunction "10_L") (pintype "bidirectional"))
    )
    (net (code "20") (name "AD04L") (class "Default")
      (node (ref "E25") (pin "3") (pinfunction "~{Q1}_3") (pintype "output"))
      (node (ref "E26") (pin "4") (pinfunction "I0_4") (pintype "input"))
      (node (ref "E26") (pin "5") (pinfunction "I1_5") (pintype "input"))
    )
    (net (code "21") (name "AD05") (class "Default")
      (node (ref "E24") (pin "12") (pinfunction "I1_12") (pintype "input"))
      (node (ref "E25") (pin "7") (pinfunction "Q2_7") (pintype "output"))
    )
    (net (code "22") (name "AD05H") (class "Default")
      (node (ref "E22") (pin "5") (pinfunction "CLAMP_5") (pintype "input"))
      (node (ref "E26") (pin "3") (pinfunction "O_3") (pintype "output"))
      (node (ref "J1") (pin "N") (pinfunction "12_N") (pintype "bidirectional"))
    )
    (net (code "23") (name "AD05L") (class "Default")
      (node (ref "E25") (pin "6") (pinfunction "~{Q2}_6") (pintype "output"))
      (node (ref "E26") (pin "1") (pinfunction "I0_1") (pintype "input"))
      (node (ref "E26") (pin "2") (pinfunction "I1_2") (pintype "input"))
    )
    (net (code "24") (name "AD06") (class "Default")
      (node (ref "E24") (pin "6") (pinfunction "I1_6") (pintype "input"))
      (node (ref "E25") (pin "15") (pinfunction "Q4_15") (pintype "output"))
    )
    (net (code "25") (name "AD06H") (class "Default")
      (node (ref "E22") (pin "7") (pinfunction "CLAMP_7") (pintype "input"))
      (node (ref "E26") (pin "8") (pinfunction "O_8") (pintype "output"))
      (node (ref "J1") (pin "R") (pinfunction "14_R") (pintype "bidirectional"))
    )
    (net (code "26") (name "AD06L") (class "Default")
      (node (ref "E25") (pin "14") (pinfunction "~{Q4}_14") (pintype "output"))
      (node (ref "E26") (pin "10") (pinfunction "I1_10") (pintype "input"))
      (node (ref "E26") (pin "9") (pinfunction "I0_9") (pintype "input"))
    )
    (net (code "27") (name "AD07") (class "Default")
      (node (ref "E24") (pin "2") (pinfunction "I0_2") (pintype "input"))
      (node (ref "E25") (pin "10") (pinfunction "Q3_10") (pintype "output"))
    )
    (net (code "28") (name "AD07H") (class "Default")
      (node (ref "E22") (pin "2") (pinfunction "CLAMP_2") (pintype "input"))
      (node (ref "E26") (pin "11") (pinfunction "O_11") (pintype "output"))
      (node (ref "J1") (pin "T") (pinfunction "16_T") (pintype "bidirectional"))
    )
    (net (code "29") (name "AD07L") (class "Default")
      (node (ref "E25") (pin "11") (pinfunction "~{Q3}_11") (pintype "output"))
      (node (ref "E26") (pin "12") (pinfunction "I0_12") (pintype "input"))
      (node (ref "E26") (pin "13") (pinfunction "I1_13") (pintype "input"))
    )
    (net (code "30") (name "AD08") (class "Default")
      (node (ref "E39") (pin "8") (pinfunction "I0_8") (pintype "input"))
      (node (ref "E40") (pin "2") (pinfunction "Q1_2") (pintype "output"))
    )
    (net (code "31") (name "AD08H") (class "Default")
      (node (ref "E41") (pin "6") (pinfunction "O_6") (pintype "output"))
      (node (ref "E46") (pin "12") (pinfunction "CLAMP_12") (pintype "input"))
      (node (ref "J1") (pin "V") (pinfunction "18_V") (pintype "bidirectional"))
    )
    (net (code "32") (name "AD08L") (class "Default")
      (node (ref "E40") (pin "3") (pinfunction "~{Q1}_3") (pintype "output"))
      (node (ref "E41") (pin "4") (pinfunction "I0_4") (pintype "input"))
      (node (ref "E41") (pin "5") (pinfunction "I1_5") (pintype "input"))
    )
    (net (code "33") (name "AD09") (class "Default")
      (node (ref "E39") (pin "12") (pinfunction "I1_12") (pintype "input"))
      (node (ref "E40") (pin "7") (pinfunction "Q2_7") (pintype "output"))
    )
    (net (code "34") (name "AD09H") (class "Default")
      (node (ref "E41") (pin "3") (pinfunction "O_3") (pintype "output"))
      (node (ref "E46") (pin "11") (pinfunction "CLAMP_11") (pintype "input"))
      (node (ref "J1") (pin "X") (pinfunction "20_X") (pintype "bidirectional"))
    )
    (net (code "35") (name "AD09L") (class "Default")
      (node (ref "E40") (pin "6") (pinfunction "~{Q2}_6") (pintype "output"))
      (node (ref "E41") (pin "1") (pinfunction "I0_1") (pintype "input"))
      (node (ref "E41") (pin "2") (pinfunction "I1_2") (pintype "input"))
    )
    (net (code "36") (name "AD10") (class "Default")
      (node (ref "E39") (pin "6") (pinfunction "I1_6") (pintype "input"))
      (node (ref "E40") (pin "15") (pinfunction "Q4_15") (pintype "output"))
    )
    (net (code "37") (name "AD10H") (class "Default")
      (node (ref "E41") (pin "8") (pinfunction "O_8") (pintype "output"))
      (node (ref "E46") (pin "9") (pinfunction "CLAMP_9") (pintype "input"))
      (node (ref "J1") (pin "Z") (pinfunction "22_Z") (pintype "bidirectional"))
    )
    (net (code "38") (name "AD10L") (class "Default")
      (node (ref "E40") (pin "14") (pinfunction "~{Q4}_14") (pintype "output"))
      (node (ref "E41") (pin "10") (pinfunction "I1_10") (pintype "input"))
      (node (ref "E41") (pin "9") (pinfunction "I0_9") (pintype "input"))
    )
    (net (code "39") (name "AD11") (class "Default")
      (node (ref "E39") (pin "2") (pinfunction "I0_2") (pintype "input"))
      (node (ref "E40") (pin "10") (pinfunction "Q3_10") (pintype "output"))
    )
    (net (code "40") (name "AD11H") (class "Default")
      (node (ref "E41") (pin "11") (pinfunction "O_11") (pintype "output"))
      (node (ref "E46") (pin "8") (pinfunction "CLAMP_8") (pintype "input"))
      (node (ref "J1") (pin "BB") (pinfunction "24_BB") (pintype "bidirectional"))
    )
    (net (code "41") (name "AD11L") (class "Default")
      (node (ref "E40") (pin "11") (pinfunction "~{Q3}_11") (pintype "output"))
      (node (ref "E41") (pin "12") (pinfunction "I0_12") (pintype "input"))
      (node (ref "E41") (pin "13") (pinfunction "I1_13") (pintype "input"))
    )
    (net (code "42") (name "ADFLAG") (class "Default")
      (node (ref "E12") (pin "9") (pinfunction "Q_9") (pintype "output"))
      (node (ref "E8") (pin "2") (pinfunction "I1_2") (pintype "input"))
      (node (ref "E8") (pin "5") (pinfunction "I1_5") (pintype "input"))
    )
    (net (code "43") (name "ADONEH") (class "Default")
      (node (ref "E23") (pin "3") (pinfunction "O_3") (pintype "output"))
      (node (ref "E47") (pin "2") (pinfunction "CLAMP_2") (pintype "input"))
      (node (ref "J1") (pin "NN") (pinfunction "34_NN") (pintype "bidirectional"))
    )
    (net (code "44") (name "ADONEL") (class "Default")
      (node (ref "E23") (pin "1") (pinfunction "I0_1") (pintype "input"))
      (node (ref "E23") (pin "11") (pinfunction "O_11") (pintype "output"))
      (node (ref "E47") (pin "3") (pinfunction "CLAMP_3") (pintype "input"))
      (node (ref "J1") (pin "RR") (pinfunction "36_RR") (pintype "bidirectional"))
    )
    (net (code "45") (name "AFLAGH") (class "Default")
      (node (ref "E43") (pin "8") (pinfunction "O_8") (pintype "output"))
      (node (ref "E47") (pin "5") (pinfunction "CLAMP_5") (pintype "input"))
      (node (ref "J1") (pin "TT") (pinfunction "38_TT") (pintype "bidirectional"))
    )
    (net (code "46") (name "AINITH") (class "Default")
      (node (ref "E27") (pin "11") (pinfunction "O_11") (pintype "output"))
      (node (ref "E47") (pin "7") (pinfunction "CLAMP_7") (pintype "input"))
      (node (ref "J1") (pin "VV") (pinfunction "40_VV") (pintype "bidirectional"))
    )
    (net (code "47") (name "AINTENH") (class "Default")
      (node (ref "E30") (pin "9") (pinfunction "Q_9") (pintype "output"))
      (node (ref "E8") (pin "1") (pinfunction "I0_1") (pintype "input"))
    )
    (net (code "48") (name "AIOT0L") (class "Default")
      (node (ref "E33") (pin "1") (pinfunction "O0_1") (pintype "output"))
      (node (ref "E34") (pin "5") (pinfunction "I1_5") (pintype "input"))
    )
    (net (code "49") (name "AIOT1L") (class "Default")
      (node (ref "E30") (pin "10") (pinfunction "PRE_10") (pintype "input"))
      (node (ref "E33") (pin "2") (pinfunction "O1_2") (pintype "output"))
    )
    (net (code "50") (name "AIOT2H") (class "Default")
      (node (ref "E3") (pin "10") (pinfunction "O_10") (pintype "output"))
      (node (ref "E8") (pin "4") (pinfunction "I0_4") (pintype "input"))
    )
    (net (code "51") (name "AIOT2L") (class "Default")
      (node (ref "E3") (pin "11") (pinfunction "I_11") (pintype "input"))
      (node (ref "E33") (pin "3") (pinfunction "O2_3") (pintype "output"))
    )
    (net (code "52") (name "AIOT3H") (class "Default")
      (node (ref "E16") (pin "9") (pinfunction "I0_9") (pintype "input"))
      (node (ref "E3") (pin "6") (pinfunction "O_6") (pintype "output"))
    )
    (net (code "53") (name "AIOT3L") (class "Default")
      (node (ref "E3") (pin "5") (pinfunction "I_5") (pintype "input"))
      (node (ref "E33") (pin "4") (pinfunction "O3_4") (pintype "output"))
      (node (ref "E34") (pin "1") (pinfunction "I0_1") (pintype "input"))
    )
    (net (code "54") (name "AIOT4L") (class "Default")
      (node (ref "E33") (pin "5") (pinfunction "O4_5") (pintype "output"))
      (node (ref "E44") (pin "10") (pinfunction "B_10") (pintype "input"))
    )
    (net (code "55") (name "AIOT5L") (class "Default")
      (node (ref "E33") (pin "6") (pinfunction "O5_6") (pintype "output"))
      (node (ref "E43") (pin "1") (pinfunction "I0_1") (pintype "input"))
      (node (ref "E43") (pin "2") (pinfunction "I1_2") (pintype "input"))
      (node (ref "E43") (pin "4") (pinfunction "I0_4") (pintype "input"))
    )
    (net (code "56") (name "AIOT6L") (class "Default")
      (node (ref "E33") (pin "7") (pinfunction "O6_7") (pintype "output"))
      (node (ref "E35") (pin "10") (pinfunction "PRE_10") (pintype "input"))
    )
    (net (code "57") (name "AIOT7L") (class "Default")
      (node (ref "E13") (pin "5") (pinfunction "I1_5") (pintype "input"))
      (node (ref "E33") (pin "9") (pinfunction "O7_9") (pintype "output"))
    )
    (net (code "58") (name "AIOTL") (class "Default")
      (node (ref "E16") (pin "2") (pinfunction "I1_2") (pintype "input"))
      (node (ref "E2") (pin "8") (pinfunction "O_8") (pintype "output"))
      (node (ref "E33") (pin "12") (pinfunction "D_12") (pintype "input"))
    )
    (net (code "59") (name "AREADY") (class "Default")
      (node (ref "E12") (pin "11") (pinfunction "CLK_11") (pintype "input"))
      (node (ref "E13") (pin "11") (pinfunction "O_11") (pintype "output"))
    )
    (net (code "60") (name "AREADYH") (class "Default")
      (node (ref "E47") (pin "8") (pinfunction "CLAMP_8") (pintype "input"))
      (node (ref "J1") (pin "LL") (pinfunction "32_LL") (pintype "bidirectional"))
      (node (ref "R5") (pin "1") (pinfunction "1_1") (pintype "passive"))
      (node (ref "R6") (pin "1") (pinfunction "1_1") (pintype "passive"))
    )
    (net (code "61") (name "AREADYL") (class "Default")
      (node (ref "E4") (pin "10") (pinfunction "I1_10") (pintype "input"))
      (node (ref "E4") (pin "12") (pinfunction "I2_12") (pintype "input"))
      (node (ref "E4") (pin "13") (pinfunction "I3_13") (pintype "input"))
      (node (ref "E4") (pin "9") (pinfunction "I0_9") (pintype "input"))
      (node (ref "E47") (pin "11") (pinfunction "CLAMP_11") (pintype "input"))
      (node (ref "J1") (pin "FF") (pinfunction "28_FF") (pintype "bidirectional"))
      (node (ref "R10") (pin "1") (pinfunction "1_1") (pintype "passive"))
    )
    (net (code "62") (name "ASTROBEH") (class "Default")
      (node (ref "E42") (pin "11") (pinfunction "O_11") (pintype "output"))
      (node (ref "E47") (pin "9") (pinfunction "CLAMP_9") (pintype "input"))
      (node (ref "J1") (pin "JJ") (pinfunction "30_JJ") (pintype "bidirectional"))
    )
    (net (code "63") (name "ASTROBEL") (class "Default")
      (node (ref "E42") (pin "6") (pinfunction "O_6") (pintype "output"))
      (node (ref "E47") (pin "12") (pinfunction "CLAMP_12") (pintype "input"))
      (node (ref "J1") (pin "DD") (pinfunction "26_DD") (pintype "bidirectional"))
    )
    (net (code "64") (name "BCTLFLGH") (class "Default")
      (node (ref "E31") (pin "2") (pinfunction "I1_2") (pintype "input"))
      (node (ref "E35") (pin "5") (pinfunction "Q_5") (pintype "output"))
    )
    (net (code "65") (name "BD00") (class "Default")
      (node (ref "E5") (pin "11") (pinfunction "O1_11") (pintype "input"))
      (node (ref "E6") (pin "15") (pinfunction "Q4_15") (pintype "output"))
    )
    (net (code "66") (name "BD00H") (class "Default")
      (node (ref "E17") (pin "11") (pinfunction "CLAMP_11") (pintype "input"))
      (node (ref "E7") (pin "11") (pinfunction "O_11") (pintype "output"))
      (node (ref "J2") (pin "B") (pinfunction "2_B") (pintype "bidirectional"))
    )
    (net (code "67") (name "BD00L") (class "Default")
      (node (ref "E6") (pin "14") (pinfunction "~{Q4}_14") (pintype "output"))
      (node (ref "E7") (pin "12") (pinfunction "I0_12") (pintype "input"))
      (node (ref "E7") (pin "13") (pinfunction "I1_13") (pintype "input"))
    )
    (net (code "68") (name "BD01") (class "Default")
      (node (ref "E5") (pin "14") (pinfunction "O0_14") (pintype "input"))
      (node (ref "E6") (pin "10") (pinfunction "Q3_10") (pintype "output"))
    )
    (net (code "69") (name "BD01H") (class "Default")
      (node (ref "E17") (pin "12") (pinfunction "CLAMP_12") (pintype "input"))
      (node (ref "E7") (pin "8") (pinfunction "O_8") (pintype "output"))
      (node (ref "J2") (pin "D") (pinfunction "4_D") (pintype "bidirectional"))
    )
    (net (code "70") (name "BD01L") (class "Default")
      (node (ref "E6") (pin "11") (pinfunction "~{Q3}_11") (pintype "output"))
      (node (ref "E7") (pin "10") (pinfunction "I1_10") (pintype "input"))
      (node (ref "E7") (pin "9") (pinfunction "I0_9") (pintype "input"))
    )
    (net (code "71") (name "BD02") (class "Default")
      (node (ref "E5") (pin "5") (pinfunction "O3_5") (pintype "input"))
      (node (ref "E6") (pin "2") (pinfunction "Q1_2") (pintype "output"))
    )
    (net (code "72") (name "BD02H") (class "Default")
      (node (ref "E17") (pin "8") (pinfunction "CLAMP_8") (pintype "input"))
      (node (ref "E7") (pin "6") (pinfunction "O_6") (pintype "output"))
      (node (ref "J2") (pin "F") (pinfunction "6_F") (pintype "bidirectional"))
    )
    (net (code "73") (name "BD02L") (class "Default")
      (node (ref "E6") (pin "3") (pinfunction "~{Q1}_3") (pintype "output"))
      (node (ref "E7") (pin "4") (pinfunction "I0_4") (pintype "input"))
      (node (ref "E7") (pin "5") (pinfunction "I1_5") (pintype "input"))
    )
    (net (code "74") (name "BD03") (class "Default")
      (node (ref "E5") (pin "2") (pinfunction "O2_2") (pintype "input"))
      (node (ref "E6") (pin "7") (pinfunction "Q2_7") (pintype "output"))
    )
    (net (code "75") (name "BD03H") (class "Default")
      (node (ref "E17") (pin "9") (pinfunction "CLAMP_9") (pintype "input"))
      (node (ref "E7") (pin "3") (pinfunction "O_3") (pintype "output"))
      (node (ref "J2") (pin "J") (pinfunction "8_J") (pintype "bidirectional"))
    )
    (net (code "76") (name "BD03L") (class "Default")
      (node (ref "E6") (pin "6") (pinfunction "~{Q2}_6") (pintype "output"))
      (node (ref "E7") (pin "1") (pinfunction "I0_1") (pintype "input"))
      (node (ref "E7") (pin "2") (pinfunction "I1_2") (pintype "input"))
    )
    (net (code "77") (name "BD04") (class "Default")
      (node (ref "E19") (pin "11") (pinfunction "O1_11") (pintype "input"))
      (node (ref "E20") (pin "15") (pinfunction "Q4_15") (pintype "output"))
    )
    (net (code "78") (name "BD04H") (class "Default")
      (node (ref "E21") (pin "8") (pinfunction "O_8") (pintype "output"))
      (node (ref "E22") (pin "9") (pinfunction "CLAMP_9") (pintype "input"))
      (node (ref "J2") (pin "L") (pinfunction "10_L") (pintype "bidirectional"))
    )
    (net (code "79") (name "BD04L") (class "Default")
      (node (ref "E20") (pin "14") (pinfunction "~{Q4}_14") (pintype "output"))
      (node (ref "E21") (pin "10") (pinfunction "I1_10") (pintype "input"))
      (node (ref "E21") (pin "9") (pinfunction "I0_9") (pintype "input"))
    )
    (net (code "80") (name "BD05") (class "Default")
      (node (ref "E19") (pin "14") (pinfunction "O0_14") (pintype "input"))
      (node (ref "E20") (pin "10") (pinfunction "Q3_10") (pintype "output"))
    )
    (net (code "81") (name "BD05H") (class "Default")
      (node (ref "E21") (pin "11") (pinfunction "O_11") (pintype "output"))
      (node (ref "E22") (pin "8") (pinfunction "CLAMP_8") (pintype "input"))
      (node (ref "J2") (pin "N") (pinfunction "12_N") (pintype "bidirectional"))
    )
    (net (code "82") (name "BD05L") (class "Default")
      (node (ref "E20") (pin "11") (pinfunction "~{Q3}_11") (pintype "output"))
      (node (ref "E21") (pin "12") (pinfunction "I0_12") (pintype "input"))
      (node (ref "E21") (pin "13") (pinfunction "I1_13") (pintype "input"))
    )
    (net (code "83") (name "BD06") (class "Default")
      (node (ref "E19") (pin "5") (pinfunction "O3_5") (pintype "input"))
      (node (ref "E20") (pin "2") (pinfunction "Q1_2") (pintype "output"))
    )
    (net (code "84") (name "BD06H") (class "Default")
      (node (ref "E21") (pin "6") (pinfunction "O_6") (pintype "output"))
      (node (ref "E22") (pin "11") (pinfunction "CLAMP_11") (pintype "input"))
      (node (ref "J2") (pin "R") (pinfunction "14_R") (pintype "bidirectional"))
    )
    (net (code "85") (name "BD06L") (class "Default")
      (node (ref "E20") (pin "3") (pinfunction "~{Q1}_3") (pintype "output"))
      (node (ref "E21") (pin "4") (pinfunction "I0_4") (pintype "input"))
      (node (ref "E21") (pin "5") (pinfunction "I1_5") (pintype "input"))
    )
    (net (code "86") (name "BD07") (class "Default")
      (node (ref "E19") (pin "2") (pinfunction "O2_2") (pintype "input"))
      (node (ref "E20") (pin "7") (pinfunction "Q2_7") (pintype "output"))
    )
    (net (code "87") (name "BD07H") (class "Default")
      (node (ref "E21") (pin "3") (pinfunction "O_3") (pintype "output"))
      (node (ref "E22") (pin "12") (pinfunction "CLAMP_12") (pintype "input"))
      (node (ref "J2") (pin "T") (pinfunction "16_T") (pintype "bidirectional"))
    )
    (net (code "88") (name "BD07L") (class "Default")
      (node (ref "E20") (pin "6") (pinfunction "~{Q2}_6") (pintype "output"))
      (node (ref "E21") (pin "1") (pinfunction "I0_1") (pintype "input"))
      (node (ref "E21") (pin "2") (pinfunction "I1_2") (pintype "input"))
    )
    (net (code "89") (name "BD08") (class "Default")
      (node (ref "E36") (pin "11") (pinfunction "O1_11") (pintype "input"))
      (node (ref "E37") (pin "15") (pinfunction "Q4_15") (pintype "output"))
    )
    (net (code "90") (name "BD08H") (class "Default")
      (node (ref "E38") (pin "8") (pinfunction "O_8") (pintype "output"))
      (node (ref "E46") (pin "2") (pinfunction "CLAMP_2") (pintype "input"))
      (node (ref "J2") (pin "V") (pinfunction "18_V") (pintype "bidirectional"))
    )
    (net (code "91") (name "BD08L") (class "Default")
      (node (ref "E37") (pin "14") (pinfunction "~{Q4}_14") (pintype "output"))
      (node (ref "E38") (pin "10") (pinfunction "I1_10") (pintype "input"))
      (node (ref "E38") (pin "9") (pinfunction "I0_9") (pintype "input"))
    )
    (net (code "92") (name "BD09") (class "Default")
      (node (ref "E36") (pin "14") (pinfunction "O0_14") (pintype "input"))
      (node (ref "E37") (pin "10") (pinfunction "Q3_10") (pintype "output"))
    )
    (net (code "93") (name "BD09H") (class "Default")
      (node (ref "E38") (pin "11") (pinfunction "O_11") (pintype "output"))
      (node (ref "E46") (pin "3") (pinfunction "CLAMP_3") (pintype "input"))
      (node (ref "J2") (pin "X") (pinfunction "20_X") (pintype "bidirectional"))
    )
    (net (code "94") (name "BD09L") (class "Default")
      (node (ref "E37") (pin "11") (pinfunction "~{Q3}_11") (pintype "output"))
      (node (ref "E38") (pin "12") (pinfunction "I0_12") (pintype "input"))
      (node (ref "E38") (pin "13") (pinfunction "I1_13") (pintype "input"))
    )
    (net (code "95") (name "BD10") (class "Default")
      (node (ref "E36") (pin "5") (pinfunction "O3_5") (pintype "input"))
      (node (ref "E37") (pin "2") (pinfunction "Q1_2") (pintype "output"))
    )
    (net (code "96") (name "BD10H") (class "Default")
      (node (ref "E38") (pin "6") (pinfunction "O_6") (pintype "output"))
      (node (ref "E46") (pin "7") (pinfunction "CLAMP_7") (pintype "input"))
      (node (ref "J2") (pin "Z") (pinfunction "22_Z") (pintype "bidirectional"))
    )
    (net (code "97") (name "BD10L") (class "Default")
      (node (ref "E37") (pin "3") (pinfunction "~{Q1}_3") (pintype "output"))
      (node (ref "E38") (pin "4") (pinfunction "I0_4") (pintype "input"))
      (node (ref "E38") (pin "5") (pinfunction "I1_5") (pintype "input"))
    )
    (net (code "98") (name "BD11") (class "Default")
      (node (ref "E36") (pin "2") (pinfunction "O2_2") (pintype "input"))
      (node (ref "E37") (pin "7") (pinfunction "Q2_7") (pintype "output"))
    )
    (net (code "99") (name "BD11H") (class "Default")
      (node (ref "E38") (pin "3") (pinfunction "O_3") (pintype "output"))
      (node (ref "E46") (pin "5") (pinfunction "CLAMP_5") (pintype "input"))
      (node (ref "J2") (pin "BB") (pinfunction "24_BB") (pintype "bidirectional"))
    )
    (net (code "100") (name "BD11L") (class "Default")
      (node (ref "E37") (pin "6") (pinfunction "~{Q2}_6") (pintype "output"))
      (node (ref "E38") (pin "1") (pinfunction "I0_1") (pintype "input"))
      (node (ref "E38") (pin "2") (pinfunction "I1_2") (pintype "input"))
    )
    (net (code "101") (name "BDFLAG") (class "Default")
      (node (ref "E12") (pin "5") (pinfunction "Q_5") (pintype "output"))
      (node (ref "E16") (pin "4") (pinfunction "I0_4") (pintype "input"))
      (node (ref "E8") (pin "12") (pinfunction "I0_12") (pintype "input"))
    )
    (net (code "102") (name "BDONEH") (class "Default")
      (node (ref "E23") (pin "8") (pinfunction "O_8") (pintype "output"))
      (node (ref "E48") (pin "2") (pinfunction "CLAMP_2") (pintype "input"))
      (node (ref "J2") (pin "NN") (pinfunction "34_NN") (pintype "bidirectional"))
    )
    (net (code "103") (name "BDONEL") (class "Default")
      (node (ref "E23") (pin "6") (pinfunction "O_6") (pintype "output"))
      (node (ref "E23") (pin "9") (pinfunction "I0_9") (pintype "input"))
      (node (ref "E48") (pin "5") (pinfunction "CLAMP_5") (pintype "input"))
      (node (ref "J2") (pin "RR") (pinfunction "36_RR") (pintype "bidirectional"))
    )
    (net (code "104") (name "BFLAGH") (class "Default")
      (node (ref "E43") (pin "11") (pinfunction "O_11") (pintype "output"))
      (node (ref "E48") (pin "8") (pinfunction "CLAMP_8") (pintype "input"))
      (node (ref "J2") (pin "TT") (pinfunction "38_TT") (pintype "bidirectional"))
    )
    (net (code "105") (name "BINITH") (class "Default")
      (node (ref "E27") (pin "6") (pinfunction "O_6") (pintype "output"))
      (node (ref "E48") (pin "7") (pinfunction "CLAMP_7") (pintype "input"))
      (node (ref "J2") (pin "VV") (pinfunction "40_VV") (pintype "bidirectional"))
    )
    (net (code "106") (name "BINTENH") (class "Default")
      (node (ref "E16") (pin "5") (pinfunction "I1_5") (pintype "input"))
      (node (ref "E30") (pin "5") (pinfunction "Q_5") (pintype "output"))
    )
    (net (code "107") (name "BIOT0L") (class "Default")
      (node (ref "E29") (pin "1") (pinfunction "O0_1") (pintype "output"))
      (node (ref "E34") (pin "12") (pinfunction "I0_12") (pintype "input"))
    )
    (net (code "108") (name "BIOT1L") (class "Default")
      (node (ref "E29") (pin "2") (pinfunction "O1_2") (pintype "output"))
      (node (ref "E30") (pin "4") (pinfunction "PRE_4") (pintype "input"))
    )
    (net (code "109") (name "BIOT2H") (class "Default")
      (node (ref "E3") (pin "12") (pinfunction "O_12") (pintype "output"))
      (node (ref "E8") (pin "13") (pinfunction "I1_13") (pintype "input"))
    )
    (net (code "110") (name "BIOT2L") (class "Default")
      (node (ref "E29") (pin "3") (pinfunction "O2_3") (pintype "output"))
      (node (ref "E3") (pin "13") (pinfunction "I_13") (pintype "input"))
    )
    (net (code "111") (name "BIOT3H") (class "Default")
      (node (ref "E16") (pin "13") (pinfunction "I1_13") (pintype "input"))
      (node (ref "E3") (pin "4") (pinfunction "O_4") (pintype "output"))
    )
    (net (code "112") (name "BIOT3L") (class "Default")
      (node (ref "E29") (pin "4") (pinfunction "O3_4") (pintype "output"))
      (node (ref "E3") (pin "3") (pinfunction "I_3") (pintype "input"))
      (node (ref "E34") (pin "9") (pinfunction "I0_9") (pintype "input"))
    )
    (net (code "113") (name "BIOT4L") (class "Default")
      (node (ref "E29") (pin "5") (pinfunction "O4_5") (pintype "output"))
      (node (ref "E44") (pin "2") (pinfunction "B_2") (pintype "input"))
    )
    (net (code "114") (name "BIOT5L") (class "Default")
      (node (ref "E19") (pin "7") (pinfunction "D0_7") (pintype "input"))
      (node (ref "E19") (pin "9") (pinfunction "D1_9") (pintype "input"))
      (node (ref "E29") (pin "6") (pinfunction "O5_6") (pintype "output"))
      (node (ref "E36") (pin "7") (pinfunction "D0_7") (pintype "input"))
      (node (ref "E36") (pin "9") (pinfunction "D1_9") (pintype "input"))
      (node (ref "E43") (pin "5") (pinfunction "I1_5") (pintype "input"))
      (node (ref "E5") (pin "7") (pinfunction "D0_7") (pintype "input"))
      (node (ref "E5") (pin "9") (pinfunction "D1_9") (pintype "input"))
    )
    (net (code "115") (name "BIOT6L") (class "Default")
      (node (ref "E29") (pin "7") (pinfunction "O6_7") (pintype "output"))
      (node (ref "E35") (pin "4") (pinfunction "PRE_4") (pintype "input"))
    )
    (net (code "116") (name "BIOT7L") (class "Default")
      (node (ref "E13") (pin "1") (pinfunction "I0_1") (pintype "input"))
      (node (ref "E29") (pin "9") (pinfunction "O7_9") (pintype "output"))
    )
    (net (code "117") (name "BIOTL") (class "Default")
      (node (ref "E1") (pin "8") (pinfunction "O_8") (pintype "output"))
      (node (ref "E16") (pin "1") (pinfunction "I0_1") (pintype "input"))
      (node (ref "E29") (pin "12") (pinfunction "D_12") (pintype "input"))
    )
    (net (code "118") (name "BREADY") (class "Default")
      (node (ref "E12") (pin "3") (pinfunction "CLK_3") (pintype "input"))
      (node (ref "E13") (pin "8") (pinfunction "O_8") (pintype "output"))
    )
    (net (code "119") (name "BREADYH") (class "Default")
      (node (ref "E48") (pin "3") (pinfunction "CLAMP_3") (pintype "input"))
      (node (ref "J2") (pin "LL") (pinfunction "32_LL") (pintype "bidirectional"))
      (node (ref "R3") (pin "1") (pinfunction "1_1") (pintype "passive"))
      (node (ref "R4") (pin "1") (pinfunction "1_1") (pintype "passive"))
    )
    (net (code "120") (name "BREADYL") (class "Default")
      (node (ref "E18") (pin "9") (pinfunction "I_9") (pintype "input"))
      (node (ref "E48") (pin "12") (pinfunction "CLAMP_12") (pintype "input"))
      (node (ref "J2") (pin "FF") (pinfunction "28_FF") (pintype "bidirectional"))
      (node (ref "R9") (pin "1") (pinfunction "1_1") (pintype "passive"))
    )
    (net (code "121") (name "BSTROBEH") (class "Default")
      (node (ref "E42") (pin "3") (pinfunction "O_3") (pintype "output"))
      (node (ref "E48") (pin "11") (pinfunction "CLAMP_11") (pintype "input"))
      (node (ref "J2") (pin "JJ") (pinfunction "30_JJ") (pintype "bidirectional"))
    )
    (net (code "122") (name "BSTROBEL") (class "Default")
      (node (ref "E42") (pin "8") (pinfunction "O_8") (pintype "output"))
      (node (ref "E48") (pin "9") (pinfunction "CLAMP_9") (pintype "input"))
      (node (ref "J2") (pin "DD") (pinfunction "26_DD") (pintype "bidirectional"))
    )
    (net (code "123") (name "DATA0") (class "Default")
      (node (ref "E10") (pin "4") (pinfunction "D1_4") (pintype "input"))
      (node (ref "E5") (pin "10") (pinfunction "I1_10") (pintype "output"))
      (node (ref "E6") (pin "13") (pinfunction "D4_13") (pintype "input"))
    )
    (net (code "124") (name "DATA1") (class "Default")
      (node (ref "E10") (pin "5") (pinfunction "D2_5") (pintype "input"))
      (node (ref "E5") (pin "13") (pinfunction "I0_13") (pintype "output"))
      (node (ref "E6") (pin "12") (pinfunction "D3_12") (pintype "input"))
    )
    (net (code "125") (name "DATA2") (class "Default")
      (node (ref "E10") (pin "13") (pinfunction "D4_13") (pintype "input"))
      (node (ref "E5") (pin "6") (pinfunction "I3_6") (pintype "output"))
      (node (ref "E6") (pin "4") (pinfunction "D1_4") (pintype "input"))
    )
    (net (code "126") (name "DATA3") (class "Default")
      (node (ref "E10") (pin "12") (pinfunction "D3_12") (pintype "input"))
      (node (ref "E5") (pin "3") (pinfunction "I2_3") (pintype "output"))
      (node (ref "E6") (pin "5") (pinfunction "D2_5") (pintype "input"))
    )
    (net (code "127") (name "DATA4") (class "Default")
      (node (ref "E19") (pin "10") (pinfunction "I1_10") (pintype "output"))
      (node (ref "E20") (pin "13") (pinfunction "D4_13") (pintype "input"))
      (node (ref "E25") (pin "4") (pinfunction "D1_4") (pintype "input"))
    )
    (net (code "128") (name "DATA5") (class "Default")
      (node (ref "E19") (pin "13") (pinfunction "I0_13") (pintype "output"))
      (node (ref "E20") (pin "12") (pinfunction "D3_12") (pintype "input"))
      (node (ref "E25") (pin "5") (pinfunction "D2_5") (pintype "input"))
    )
    (net (code "129") (name "DATA6") (class "Default")
      (node (ref "E19") (pin "6") (pinfunction "I3_6") (pintype "output"))
      (node (ref "E20") (pin "4") (pinfunction "D1_4") (pintype "input"))
      (node (ref "E25") (pin "13") (pinfunction "D4_13") (pintype "input"))
    )
    (net (code "130") (name "DATA7") (class "Default")
      (node (ref "E19") (pin "3") (pinfunction "I2_3") (pintype "output"))
      (node (ref "E20") (pin "5") (pinfunction "D2_5") (pintype "input"))
      (node (ref "E25") (pin "12") (pinfunction "D3_12") (pintype "input"))
    )
    (net (code "131") (name "DATA8") (class "Default")
      (node (ref "E36") (pin "10") (pinfunction "I1_10") (pintype "output"))
      (node (ref "E37") (pin "13") (pinfunction "D4_13") (pintype "input"))
      (node (ref "E40") (pin "4") (pinfunction "D1_4") (pintype "input"))
    )
    (net (code "132") (name "DATA9") (class "Default")
      (node (ref "E36") (pin "13") (pinfunction "I0_13") (pintype "output"))
      (node (ref "E37") (pin "12") (pinfunction "D3_12") (pintype "input"))
      (node (ref "E40") (pin "5") (pinfunction "D2_5") (pintype "input"))
    )
    (net (code "133") (name "DATA10") (class "Default")
      (node (ref "E36") (pin "6") (pinfunction "I3_6") (pintype "output"))
      (node (ref "E37") (pin "4") (pinfunction "D1_4") (pintype "input"))
      (node (ref "E40") (pin "13") (pinfunction "D4_13") (pintype "input"))
    )
    (net (code "134") (name "DATA11") (class "Default")
      (node (ref "E36") (pin "3") (pinfunction "I2_3") (pintype "output"))
      (node (ref "E37") (pin "5") (pinfunction "D2_5") (pintype "input"))
      (node (ref "E40") (pin "12") (pinfunction "D3_12") (pintype "input"))
    )
    (net (code "135") (name "GND") (class "Default")
      (node (ref "C1") (pin "2") (pinfunction "2_2") (pintype "passive"))
      (node (ref "C10") (pin "2") (pinfunction "2_2") (pintype "passive"))
      (node (ref "C100") (pin "-") (pinfunction "-_-") (pintype "passive"))
      (node (ref "C101") (pin "-") (pinfunction "-_-") (pintype "passive"))
      (node (ref "C102") (pin "-") (pinfunction "-_-") (pintype "passive"))
      (node (ref "C11") (pin "2") (pinfunction "2_2") (pintype "passive"))
      (node (ref "C12") (pin "2") (pinfunction "2_2") (pintype "passive"))
      (node (ref "C13") (pin "2") (pinfunction "2_2") (pintype "passive"))
      (node (ref "C14") (pin "2") (pinfunction "2_2") (pintype "passive"))
      (node (ref "C15") (pin "2") (pinfunction "2_2") (pintype "passive"))
      (node (ref "C16") (pin "2") (pinfunction "2_2") (pintype "passive"))
      (node (ref "C17") (pin "2") (pinfunction "2_2") (pintype "passive"))
      (node (ref "C18") (pin "2") (pinfunction "2_2") (pintype "passive"))
      (node (ref "C19") (pin "2") (pinfunction "2_2") (pintype "passive"))
      (node (ref "C2") (pin "2") (pinfunction "2_2") (pintype "passive"))
      (node (ref "C20") (pin "2") (pinfunction "2_2") (pintype "passive"))
      (node (ref "C21") (pin "2") (pinfunction "2_2") (pintype "passive"))
      (node (ref "C22") (pin "2") (pinfunction "2_2") (pintype "passive"))
      (node (ref "C23") (pin "2") (pinfunction "2_2") (pintype "passive"))
      (node (ref "C24") (pin "2") (pinfunction "2_2") (pintype "passive"))
      (node (ref "C25") (pin "2") (pinfunction "2_2") (pintype "passive"))
      (node (ref "C26") (pin "2") (pinfunction "2_2") (pintype "passive"))
      (node (ref "C27") (pin "2") (pinfunction "2_2") (pintype "passive"))
      (node (ref "C28") (pin "2") (pinfunction "2_2") (pintype "passive"))
      (node (ref "C29") (pin "2") (pinfunction "2_2") (pintype "passive"))
      (node (ref "C3") (pin "2") (pinfunction "2_2") (pintype "passive"))
      (node (ref "C30") (pin "2") (pinfunction "2_2") (pintype "passive"))
      (node (ref "C31") (pin "2") (pinfunction "2_2") (pintype "passive"))
      (node (ref "C32") (pin "2") (pinfunction "2_2") (pintype "passive"))
      (node (ref "C33") (pin "2") (pinfunction "2_2") (pintype "passive"))
      (node (ref "C34") (pin "2") (pinfunction "2_2") (pintype "passive"))
      (node (ref "C4") (pin "2") (pinfunction "2_2") (pintype "passive"))
      (node (ref "C5") (pin "2") (pinfunction "2_2") (pintype "passive"))
      (node (ref "C6") (pin "2") (pinfunction "2_2") (pintype "passive"))
      (node (ref "C7") (pin "2") (pinfunction "2_2") (pintype "passive"))
      (node (ref "C8") (pin "2") (pinfunction "2_2") (pintype "passive"))
      (node (ref "C9") (pin "2") (pinfunction "2_2") (pintype "passive"))
      (node (ref "E14") (pin "7") (pinfunction "FORCE0_7") (pintype "input"))
      (node (ref "E14") (pin "9") (pinfunction "FORCE0_9") (pintype "input"))
      (node (ref "E32") (pin "7") (pinfunction "FORCE0_7") (pintype "input"))
      (node (ref "E32") (pin "9") (pinfunction "FORCE0_9") (pintype "input"))
      (node (ref "E44") (pin "1") (pinfunction "A_1") (pintype "input"))
      (node (ref "E44") (pin "9") (pinfunction "A_9") (pintype "input"))
      (node (ref "J1") (pin "A") (pinfunction "1_A") (pintype "bidirectional"))
      (node (ref "J1") (pin "AA") (pinfunction "23_AA") (pintype "bidirectional"))
      (node (ref "J1") (pin "C") (pinfunction "3_C") (pintype "bidirectional"))
      (node (ref "J1") (pin "CC") (pinfunction "25_CC") (pintype "bidirectional"))
      (node (ref "J1") (pin "E") (pinfunction "5_E") (pintype "bidirectional"))
      (node (ref "J1") (pin "EE") (pinfunction "27_EE") (pintype "bidirectional"))
      (node (ref "J1") (pin "H") (pinfunction "7_H") (pintype "bidirectional"))
      (node (ref "J1") (pin "HH") (pinfunction "29_HH") (pintype "bidirectional"))
      (node (ref "J1") (pin "K") (pinfunction "9_K") (pintype "bidirectional"))
      (node (ref "J1") (pin "KK") (pinfunction "31_KK") (pintype "bidirectional"))
      (node (ref "J1") (pin "M") (pinfunction "11_M") (pintype "bidirectional"))
      (node (ref "J1") (pin "MM") (pinfunction "33_MM") (pintype "bidirectional"))
      (node (ref "J1") (pin "P") (pinfunction "13_P") (pintype "bidirectional"))
      (node (ref "J1") (pin "PP") (pinfunction "35_PP") (pintype "bidirectional"))
      (node (ref "J1") (pin "S") (pinfunction "15_S") (pintype "bidirectional"))
      (node (ref "J1") (pin "SS") (pinfunction "37_SS") (pintype "bidirectional"))
      (node (ref "J1") (pin "U") (pinfunction "17_U") (pintype "bidirectional"))
      (node (ref "J1") (pin "UU") (pinfunction "39_UU") (pintype "bidirectional"))
      (node (ref "J1") (pin "W") (pinfunction "19_W") (pintype "bidirectional"))
      (node (ref "J1") (pin "Y") (pinfunction "21_Y") (pintype "bidirectional"))
      (node (ref "J2") (pin "A") (pinfunction "1_A") (pintype "bidirectional"))
      (node (ref "J2") (pin "AA") (pinfunction "23_AA") (pintype "bidirectional"))
      (node (ref "J2") (pin "C") (pinfunction "3_C") (pintype "bidirectional"))
      (node (ref "J2") (pin "CC") (pinfunction "25_CC") (pintype "bidirectional"))
      (node (ref "J2") (pin "E") (pinfunction "5_E") (pintype "bidirectional"))
      (node (ref "J2") (pin "EE") (pinfunction "27_EE") (pintype "bidirectional"))
      (node (ref "J2") (pin "H") (pinfunction "7_H") (pintype "bidirectional"))
      (node (ref "J2") (pin "HH") (pinfunction "29_HH") (pintype "bidirectional"))
      (node (ref "J2") (pin "K") (pinfunction "9_K") (pintype "bidirectional"))
      (node (ref "J2") (pin "KK") (pinfunction "31_KK") (pintype "bidirectional"))
      (node (ref "J2") (pin "M") (pinfunction "11_M") (pintype "bidirectional"))
      (node (ref "J2") (pin "MM") (pinfunction "33_MM") (pintype "bidirectional"))
      (node (ref "J2") (pin "P") (pinfunction "13_P") (pintype "bidirectional"))
      (node (ref "J2") (pin "PP") (pinfunction "35_PP") (pintype "bidirectional"))
      (node (ref "J2") (pin "S") (pinfunction "15_S") (pintype "bidirectional"))
      (node (ref "J2") (pin "SS") (pinfunction "37_SS") (pintype "bidirectional"))
      (node (ref "J2") (pin "U") (pinfunction "17_U") (pintype "bidirectional"))
      (node (ref "J2") (pin "UU") (pinfunction "39_UU") (pintype "bidirectional"))
      (node (ref "J2") (pin "W") (pinfunction "19_W") (pintype "bidirectional"))
      (node (ref "J2") (pin "Y") (pinfunction "21_Y") (pintype "bidirectional"))
      (node (ref "R14") (pin "1") (pinfunction "1_1") (pintype "passive"))
      (node (ref "R16") (pin "1") (pinfunction "1_1") (pintype "passive"))
      (node (ref "R18") (pin "1") (pinfunction "1_1") (pintype "passive"))
      (node (ref "R2") (pin "2") (pinfunction "2_2") (pintype "passive"))
      (node (ref "R20") (pin "1") (pinfunction "1_1") (pintype "passive"))
      (node (ref "U$2") (pin "AC1") (pinfunction "1_AC1") (pintype "bidirectional"))
      (node (ref "U$2") (pin "AC2") (pinfunction "1_AC2") (pintype "bidirectional"))
      (node (ref "U$2") (pin "AF1") (pinfunction "1_AF1") (pintype "bidirectional"))
      (node (ref "U$2") (pin "AF2") (pinfunction "1_AF2") (pintype "bidirectional"))
      (node (ref "U$2") (pin "AN1") (pinfunction "1_AN1") (pintype "bidirectional"))
      (node (ref "U$2") (pin "AN2") (pinfunction "1_AN2") (pintype "bidirectional"))
      (node (ref "U$2") (pin "AT1") (pinfunction "1_AT1") (pintype "bidirectional"))
      (node (ref "U$2") (pin "AT2") (pinfunction "1_AT2") (pintype "bidirectional"))
      (node (ref "U$2") (pin "BC1") (pinfunction "1_BC1") (pintype "bidirectional"))
      (node (ref "U$2") (pin "BC2") (pinfunction "1_BC2") (pintype "bidirectional"))
      (node (ref "U$2") (pin "BF1") (pinfunction "1_BF1") (pintype "bidirectional"))
      (node (ref "U$2") (pin "BF2") (pinfunction "1_BF2") (pintype "bidirectional"))
      (node (ref "U$2") (pin "BN1") (pinfunction "1_BN1") (pintype "bidirectional"))
      (node (ref "U$2") (pin "BN2") (pinfunction "1_BN2") (pintype "bidirectional"))
      (node (ref "U$2") (pin "BT1") (pinfunction "1_BT1") (pintype "bidirectional"))
      (node (ref "U$2") (pin "BT2") (pinfunction "1_BT2") (pintype "bidirectional"))
      (node (ref "U$2") (pin "CC1") (pinfunction "1_CC1") (pintype "bidirectional"))
      (node (ref "U$2") (pin "CC2") (pinfunction "1_CC2") (pintype "bidirectional"))
      (node (ref "U$2") (pin "CF1") (pinfunction "1_CF1") (pintype "bidirectional"))
      (node (ref "U$2") (pin "CF2") (pinfunction "1_CF2") (pintype "bidirectional"))
      (node (ref "U$2") (pin "CN1") (pinfunction "1_CN1") (pintype "bidirectional"))
      (node (ref "U$2") (pin "CN2") (pinfunction "1_CN2") (pintype "bidirectional"))
      (node (ref "U$2") (pin "CT1") (pinfunction "1_CT1") (pintype "bidirectional"))
      (node (ref "U$2") (pin "CT2") (pinfunction "1_CT2") (pintype "bidirectional"))
      (node (ref "U$2") (pin "DC1") (pinfunction "1_DC1") (pintype "bidirectional"))
      (node (ref "U$2") (pin "DC2") (pinfunction "1_DC2") (pintype "bidirectional"))
      (node (ref "U$2") (pin "DF1") (pinfunction "1_DF1") (pintype "bidirectional"))
      (node (ref "U$2") (pin "DF2") (pinfunction "1_DF2") (pintype "bidirectional"))
      (node (ref "U$2") (pin "DN1") (pinfunction "1_DN1") (pintype "bidirectional"))
      (node (ref "U$2") (pin "DN2") (pinfunction "1_DN2") (pintype "bidirectional"))
      (node (ref "U$2") (pin "DT1") (pinfunction "1_DT1") (pintype "bidirectional"))
      (node (ref "U$2") (pin "DT2") (pinfunction "1_DT2") (pintype "bidirectional"))
      (node (ref "W29") (pin "1") (pinfunction "1_1") (pintype "passive"))
      (node (ref "W30") (pin "1") (pinfunction "1_1") (pintype "passive"))
      (node (ref "W31") (pin "1") (pinfunction "1_1") (pintype "passive"))
      (node (ref "W32") (pin "1") (pinfunction "1_1") (pintype "passive"))
    )
    (net (code "136") (name "INITIALIZE") (class "Default")
      (node (ref "E32") (pin "3") (pinfunction "Y2_3") (pintype "input"))
      (node (ref "U$2") (pin "CR1") (pinfunction "1_CR1") (pintype "bidirectional"))
    )
    (net (code "137") (name "INITIALIZEH") (class "Default")
      (node (ref "E27") (pin "1") (pinfunction "I0_1") (pintype "input"))
      (node (ref "E27") (pin "2") (pinfunction "I1_2") (pintype "input"))
      (node (ref "E45") (pin "4") (pinfunction "O_4") (pintype "open_collector"))
      (node (ref "R1") (pin "1") (pinfunction "1_1") (pintype "passive"))
      (node (ref "R2") (pin "1") (pinfunction "1_1") (pintype "passive"))
    )
    (net (code "138") (name "INITIALIZEL") (class "Default")
      (node (ref "E32") (pin "4") (pinfunction "A2_4") (pintype "output"))
      (node (ref "E34") (pin "10") (pinfunction "I1_10") (pintype "input"))
      (node (ref "E34") (pin "13") (pinfunction "I1_13") (pintype "input"))
      (node (ref "E34") (pin "2") (pinfunction "I1_2") (pintype "input"))
      (node (ref "E34") (pin "4") (pinfunction "I0_4") (pintype "input"))
      (node (ref "E45") (pin "5") (pinfunction "I0_5") (pintype "input"))
      (node (ref "E45") (pin "6") (pinfunction "I1_6") (pintype "input"))
    )
    (net (code "139") (name "INITL") (class "Default")
      (node (ref "E10") (pin "1") (pinfunction "CLR_1") (pintype "input"))
      (node (ref "E13") (pin "2") (pinfunction "I1_2") (pintype "input"))
      (node (ref "E13") (pin "4") (pinfunction "I0_4") (pintype "input"))
      (node (ref "E20") (pin "1") (pinfunction "CLR_1") (pintype "input"))
      (node (ref "E25") (pin "1") (pinfunction "CLR_1") (pintype "input"))
      (node (ref "E27") (pin "12") (pinfunction "I0_12") (pintype "input"))
      (node (ref "E27") (pin "13") (pinfunction "I1_13") (pintype "input"))
      (node (ref "E27") (pin "3") (pinfunction "O_3") (pintype "output"))
      (node (ref "E27") (pin "4") (pinfunction "I0_4") (pintype "input"))
      (node (ref "E27") (pin "5") (pinfunction "I1_5") (pintype "input"))
      (node (ref "E37") (pin "1") (pinfunction "CLR_1") (pintype "input"))
      (node (ref "E40") (pin "1") (pinfunction "CLR_1") (pintype "input"))
      (node (ref "E6") (pin "1") (pinfunction "CLR_1") (pintype "input"))
    )
    (net (code "140") (name "IO_PAUSEH") (class "Default")
      (node (ref "E1") (pin "5") (pinfunction "I4_5") (pintype "input"))
      (node (ref "E1") (pin "6") (pinfunction "I5_6") (pintype "input"))
      (node (ref "E14") (pin "2") (pinfunction "A1_2") (pintype "output"))
      (node (ref "E2") (pin "5") (pinfunction "I4_5") (pintype "input"))
      (node (ref "E2") (pin "6") (pinfunction "I5_6") (pintype "input"))
    )
    (net (code "141") (name "MD03H") (class "Default")
      (node (ref "E14") (pin "10") (pinfunction "A1_10") (pintype "output"))
      (node (ref "E15") (pin "13") (pinfunction "I_13") (pintype "input"))
      (node (ref "W1") (pin "1") (pinfunction "1_1") (pintype "passive"))
      (node (ref "W13") (pin "1") (pinfunction "1_1") (pintype "passive"))
    )
    (net (code "142") (name "MD03L") (class "Default")
      (node (ref "E15") (pin "12") (pinfunction "O_12") (pintype "output"))
      (node (ref "W14") (pin "1") (pinfunction "1_1") (pintype "passive"))
      (node (ref "W2") (pin "1") (pinfunction "1_1") (pintype "passive"))
    )
    (net (code "143") (name "MD04H") (class "Default")
      (node (ref "E14") (pin "6") (pinfunction "A3_6") (pintype "output"))
      (node (ref "E15") (pin "1") (pinfunction "I_1") (pintype "input"))
      (node (ref "W15") (pin "1") (pinfunction "1_1") (pintype "passive"))
      (node (ref "W3") (pin "1") (pinfunction "1_1") (pintype "passive"))
    )
    (net (code "144") (name "MD04L") (class "Default")
      (node (ref "E15") (pin "2") (pinfunction "O_2") (pintype "output"))
      (node (ref "W16") (pin "1") (pinfunction "1_1") (pintype "passive"))
      (node (ref "W4") (pin "1") (pinfunction "1_1") (pintype "passive"))
    )
    (net (code "145") (name "MD05H") (class "Default")
      (node (ref "E14") (pin "4") (pinfunction "A2_4") (pintype "output"))
      (node (ref "E15") (pin "3") (pinfunction "I_3") (pintype "input"))
      (node (ref "W17") (pin "1") (pinfunction "1_1") (pintype "passive"))
      (node (ref "W5") (pin "1") (pinfunction "1_1") (pintype "passive"))
    )
    (net (code "146") (name "MD05L") (class "Default")
      (node (ref "E15") (pin "4") (pinfunction "O_4") (pintype "output"))
      (node (ref "W18") (pin "1") (pinfunction "1_1") (pintype "passive"))
      (node (ref "W6") (pin "1") (pinfunction "1_1") (pintype "passive"))
    )
    (net (code "147") (name "MD06H") (class "Default")
      (node (ref "E14") (pin "12") (pinfunction "A2_12") (pintype "output"))
      (node (ref "E15") (pin "11") (pinfunction "I_11") (pintype "input"))
      (node (ref "W19") (pin "1") (pinfunction "1_1") (pintype "passive"))
      (node (ref "W7") (pin "1") (pinfunction "1_1") (pintype "passive"))
    )
    (net (code "148") (name "MD06L") (class "Default")
      (node (ref "E15") (pin "10") (pinfunction "O_10") (pintype "output"))
      (node (ref "W20") (pin "1") (pinfunction "1_1") (pintype "passive"))
      (node (ref "W8") (pin "1") (pinfunction "1_1") (pintype "passive"))
    )
    (net (code "149") (name "MD07H") (class "Default")
      (node (ref "E14") (pin "14") (pinfunction "A3_14") (pintype "output"))
      (node (ref "E15") (pin "9") (pinfunction "I_9") (pintype "input"))
      (node (ref "W21") (pin "1") (pinfunction "1_1") (pintype "passive"))
      (node (ref "W9") (pin "1") (pinfunction "1_1") (pintype "passive"))
    )
    (net (code "150") (name "MD07L") (class "Default")
      (node (ref "E15") (pin "8") (pinfunction "O_8") (pintype "output"))
      (node (ref "W10") (pin "1") (pinfunction "1_1") (pintype "passive"))
      (node (ref "W22") (pin "1") (pinfunction "1_1") (pintype "passive"))
    )
    (net (code "151") (name "MD08H") (class "Default")
      (node (ref "E15") (pin "5") (pinfunction "I_5") (pintype "input"))
      (node (ref "E32") (pin "2") (pinfunction "A1_2") (pintype "output"))
      (node (ref "W11") (pin "1") (pinfunction "1_1") (pintype "passive"))
      (node (ref "W23") (pin "1") (pinfunction "1_1") (pintype "passive"))
    )
    (net (code "152") (name "MD08L") (class "Default")
      (node (ref "E15") (pin "6") (pinfunction "O_6") (pintype "output"))
      (node (ref "W12") (pin "1") (pinfunction "1_1") (pintype "passive"))
      (node (ref "W24") (pin "1") (pinfunction "1_1") (pintype "passive"))
    )
    (net (code "153") (name "MD09H") (class "Default")
      (node (ref "E29") (pin "13") (pinfunction "C_13") (pintype "input"))
      (node (ref "E32") (pin "14") (pinfunction "A3_14") (pintype "output"))
      (node (ref "E33") (pin "13") (pinfunction "C_13") (pintype "input"))
    )
    (net (code "154") (name "MD10H") (class "Default")
      (node (ref "E29") (pin "14") (pinfunction "B_14") (pintype "input"))
      (node (ref "E32") (pin "12") (pinfunction "A2_12") (pintype "output"))
      (node (ref "E33") (pin "14") (pinfunction "B_14") (pintype "input"))
    )
    (net (code "155") (name "MD11H") (class "Default")
      (node (ref "E29") (pin "15") (pinfunction "A_15") (pintype "input"))
      (node (ref "E32") (pin "10") (pinfunction "A1_10") (pintype "output"))
      (node (ref "E33") (pin "15") (pinfunction "A_15") (pintype "input"))
    )
    (net (code "156") (name "Net-(E1A-I0)") (class "Default")
      (node (ref "E1") (pin "1") (pinfunction "I0_1") (pintype "input"))
      (node (ref "W13") (pin "2") (pinfunction "2_2") (pintype "passive"))
      (node (ref "W14") (pin "2") (pinfunction "2_2") (pintype "passive"))
    )
    (net (code "157") (name "Net-(E1A-I1)") (class "Default")
      (node (ref "E1") (pin "2") (pinfunction "I1_2") (pintype "input"))
      (node (ref "W19") (pin "2") (pinfunction "2_2") (pintype "passive"))
      (node (ref "W20") (pin "2") (pinfunction "2_2") (pintype "passive"))
    )
    (net (code "158") (name "Net-(E1A-I2)") (class "Default")
      (node (ref "E1") (pin "3") (pinfunction "I2_3") (pintype "input"))
      (node (ref "W17") (pin "2") (pinfunction "2_2") (pintype "passive"))
      (node (ref "W18") (pin "2") (pinfunction "2_2") (pintype "passive"))
    )
    (net (code "159") (name "Net-(E1A-I3)") (class "Default")
      (node (ref "E1") (pin "4") (pinfunction "I3_4") (pintype "input"))
      (node (ref "W15") (pin "2") (pinfunction "2_2") (pintype "passive"))
      (node (ref "W16") (pin "2") (pinfunction "2_2") (pintype "passive"))
    )
    (net (code "160") (name "Net-(E1A-I6)") (class "Default")
      (node (ref "E1") (pin "11") (pinfunction "I6_11") (pintype "input"))
      (node (ref "W23") (pin "2") (pinfunction "2_2") (pintype "passive"))
      (node (ref "W24") (pin "2") (pinfunction "2_2") (pintype "passive"))
    )
    (net (code "161") (name "Net-(E1A-I7)") (class "Default")
      (node (ref "E1") (pin "12") (pinfunction "I7_12") (pintype "input"))
      (node (ref "W21") (pin "2") (pinfunction "2_2") (pintype "passive"))
      (node (ref "W22") (pin "2") (pinfunction "2_2") (pintype "passive"))
    )
    (net (code "162") (name "Net-(E2A-I0)") (class "Default")
      (node (ref "E2") (pin "1") (pinfunction "I0_1") (pintype "input"))
      (node (ref "W5") (pin "2") (pinfunction "2_2") (pintype "passive"))
      (node (ref "W6") (pin "2") (pinfunction "2_2") (pintype "passive"))
    )
    (net (code "163") (name "Net-(E2A-I1)") (class "Default")
      (node (ref "E2") (pin "2") (pinfunction "I1_2") (pintype "input"))
      (node (ref "W1") (pin "2") (pinfunction "2_2") (pintype "passive"))
      (node (ref "W2") (pin "2") (pinfunction "2_2") (pintype "passive"))
    )
    (net (code "164") (name "Net-(E2A-I2)") (class "Default")
      (node (ref "E2") (pin "3") (pinfunction "I2_3") (pintype "input"))
      (node (ref "W7") (pin "2") (pinfunction "2_2") (pintype "passive"))
      (node (ref "W8") (pin "2") (pinfunction "2_2") (pintype "passive"))
    )
    (net (code "165") (name "Net-(E2A-I3)") (class "Default")
      (node (ref "E2") (pin "4") (pinfunction "I3_4") (pintype "input"))
      (node (ref "W3") (pin "2") (pinfunction "2_2") (pintype "passive"))
      (node (ref "W4") (pin "2") (pinfunction "2_2") (pintype "passive"))
    )
    (net (code "166") (name "Net-(E2A-I6)") (class "Default")
      (node (ref "E2") (pin "11") (pinfunction "I6_11") (pintype "input"))
      (node (ref "W10") (pin "2") (pinfunction "2_2") (pintype "passive"))
      (node (ref "W9") (pin "2") (pinfunction "2_2") (pintype "passive"))
    )
    (net (code "167") (name "Net-(E2A-I7)") (class "Default")
      (node (ref "E2") (pin "12") (pinfunction "I7_12") (pintype "input"))
      (node (ref "W11") (pin "2") (pinfunction "2_2") (pintype "passive"))
      (node (ref "W12") (pin "2") (pinfunction "2_2") (pintype "passive"))
    )
    (net (code "168") (name "Net-(E3D-I)") (class "Default")
      (node (ref "E3") (pin "9") (pinfunction "I_9") (pintype "input"))
      (node (ref "E4") (pin "6") (pinfunction "O_6") (pintype "output"))
    )
    (net (code "169") (name "Net-(E4A-I0)") (class "Default")
      (node (ref "C34") (pin "1") (pinfunction "1_1") (pintype "passive"))
      (node (ref "E4") (pin "1") (pinfunction "I0_1") (pintype "input"))
      (node (ref "E4") (pin "2") (pinfunction "I1_2") (pintype "input"))
      (node (ref "E4") (pin "4") (pinfunction "I2_4") (pintype "input"))
      (node (ref "E4") (pin "5") (pinfunction "I3_5") (pintype "input"))
      (node (ref "R6") (pin "2") (pinfunction "2_2") (pintype "passive"))
    )
    (net (code "170") (name "Net-(E8B-O)") (class "Default")
      (node (ref "E8") (pin "6") (pinfunction "O_6") (pintype "output"))
      (node (ref "E8") (pin "9") (pinfunction "I0_9") (pintype "input"))
    )
    (net (code "171") (name "Net-(E8C-I1)") (class "Default")
      (node (ref "E8") (pin "10") (pinfunction "I1_10") (pintype "input"))
      (node (ref "E8") (pin "11") (pinfunction "O_11") (pintype "output"))
    )
    (net (code "172") (name "Net-(E10A-CLK)") (class "Default")
      (node (ref "E10") (pin "9") (pinfunction "CLK_9") (pintype "input"))
      (node (ref "E18") (pin "2") (pinfunction "O_2") (pintype "output"))
      (node (ref "E25") (pin "9") (pinfunction "CLK_9") (pintype "input"))
      (node (ref "E40") (pin "9") (pinfunction "CLK_9") (pintype "input"))
    )
    (net (code "173") (name "Net-(E12A-CLR)") (class "Default")
      (node (ref "E12") (pin "1") (pinfunction "CLR_1") (pintype "input"))
      (node (ref "E23") (pin "5") (pinfunction "I1_5") (pintype "input"))
      (node (ref "E34") (pin "8") (pinfunction "O_8") (pintype "output"))
    )
    (net (code "174") (name "Net-(E12A-~{Q})") (class "Default")
      (node (ref "E12") (pin "6") (pinfunction "~{Q}_6") (pintype "output"))
      (node (ref "E23") (pin "4") (pinfunction "I0_4") (pintype "input"))
    )
    (net (code "175") (name "Net-(E12B-CLR)") (class "Default")
      (node (ref "E12") (pin "13") (pinfunction "CLR_13") (pintype "input"))
      (node (ref "E23") (pin "13") (pinfunction "I1_13") (pintype "input"))
      (node (ref "E34") (pin "3") (pinfunction "O_3") (pintype "output"))
    )
    (net (code "176") (name "Net-(E12B-~{Q})") (class "Default")
      (node (ref "E12") (pin "8") (pinfunction "~{Q}_8") (pintype "output"))
      (node (ref "E23") (pin "12") (pinfunction "I0_12") (pintype "input"))
    )
    (net (code "177") (name "Net-(E13A-O)") (class "Default")
      (node (ref "E13") (pin "3") (pinfunction "O_3") (pintype "output"))
      (node (ref "E35") (pin "1") (pinfunction "CLR_1") (pintype "input"))
    )
    (net (code "178") (name "Net-(E13B-O)") (class "Default")
      (node (ref "E13") (pin "6") (pinfunction "O_6") (pintype "output"))
      (node (ref "E35") (pin "13") (pinfunction "CLR_13") (pintype "input"))
    )
    (net (code "179") (name "Net-(E13C-I0)") (class "Default")
      (node (ref "E13") (pin "9") (pinfunction "I0_9") (pintype "input"))
      (node (ref "E31") (pin "8") (pinfunction "O_8") (pintype "output"))
    )
    (net (code "180") (name "Net-(E13C-I1)") (class "Default")
      (node (ref "E13") (pin "10") (pinfunction "I1_10") (pintype "input"))
      (node (ref "E3") (pin "2") (pinfunction "O_2") (pintype "output"))
    )
    (net (code "181") (name "Net-(E13D-I0)") (class "Default")
      (node (ref "E13") (pin "12") (pinfunction "I0_12") (pintype "input"))
      (node (ref "E31") (pin "11") (pinfunction "O_11") (pintype "output"))
    )
    (net (code "182") (name "Net-(E13D-I1)") (class "Default")
      (node (ref "E13") (pin "13") (pinfunction "I1_13") (pintype "input"))
      (node (ref "E3") (pin "8") (pinfunction "O_8") (pintype "output"))
    )
    (net (code "183") (name "Net-(E16A-O)") (class "Default")
      (node (ref "E16") (pin "3") (pinfunction "O_3") (pintype "output"))
      (node (ref "E28") (pin "11") (pinfunction "I0_11") (pintype "input"))
      (node (ref "E28") (pin "12") (pinfunction "I1_12") (pintype "input"))
    )
    (net (code "184") (name "Net-(E16B-O)") (class "Default")
      (node (ref "E16") (pin "6") (pinfunction "O_6") (pintype "output"))
      (node (ref "E27") (pin "10") (pinfunction "I1_10") (pintype "input"))
    )
    (net (code "185") (name "Net-(E16C-O)") (class "Default")
      (node (ref "E16") (pin "8") (pinfunction "O_8") (pintype "output"))
      (node (ref "E18") (pin "1") (pinfunction "I_1") (pintype "input"))
    )
    (net (code "186") (name "Net-(E16D-O)") (class "Default")
      (node (ref "E16") (pin "11") (pinfunction "O_11") (pintype "output"))
      (node (ref "E18") (pin "3") (pinfunction "I_3") (pintype "input"))
    )
    (net (code "187") (name "Net-(E18C-O)") (class "Default")
      (node (ref "E18") (pin "8") (pinfunction "O_8") (pintype "output"))
      (node (ref "E31") (pin "9") (pinfunction "I0_9") (pintype "input"))
    )
    (net (code "188") (name "Net-(E18E-O)") (class "Default")
      (node (ref "E18") (pin "4") (pinfunction "O_4") (pintype "output"))
      (node (ref "E20") (pin "9") (pinfunction "CLK_9") (pintype "input"))
      (node (ref "E37") (pin "9") (pinfunction "CLK_9") (pintype "input"))
      (node (ref "E6") (pin "9") (pinfunction "CLK_9") (pintype "input"))
    )
    (net (code "189") (name "Net-(E18F-I)") (class "Default")
      (node (ref "C33") (pin "1") (pinfunction "1_1") (pintype "passive"))
      (node (ref "E18") (pin "5") (pinfunction "I_5") (pintype "input"))
      (node (ref "R4") (pin "2") (pinfunction "2_2") (pintype "passive"))
    )
    (net (code "190") (name "Net-(E18F-O)") (class "Default")
      (node (ref "E18") (pin "6") (pinfunction "O_6") (pintype "output"))
      (node (ref "E3") (pin "1") (pinfunction "I_1") (pintype "input"))
    )
    (net (code "191") (name "Net-(E24A-I1)") (class "Default")
      (node (ref "E24") (pin "11") (pinfunction "I0_11") (pintype "input"))
      (node (ref "E24") (pin "3") (pinfunction "I1_3") (pintype "input"))
      (node (ref "E24") (pin "5") (pinfunction "I0_5") (pintype "input"))
      (node (ref "E24") (pin "9") (pinfunction "I1_9") (pintype "input"))
      (node (ref "E39") (pin "11") (pinfunction "I0_11") (pintype "input"))
      (node (ref "E39") (pin "3") (pinfunction "I1_3") (pintype "input"))
      (node (ref "E39") (pin "5") (pinfunction "I0_5") (pintype "input"))
      (node (ref "E39") (pin "9") (pinfunction "I1_9") (pintype "input"))
      (node (ref "E43") (pin "3") (pinfunction "O_3") (pintype "output"))
      (node (ref "E9") (pin "11") (pinfunction "I0_11") (pintype "input"))
      (node (ref "E9") (pin "3") (pinfunction "I1_3") (pintype "input"))
      (node (ref "E9") (pin "5") (pinfunction "I0_5") (pintype "input"))
      (node (ref "E9") (pin "9") (pinfunction "I1_9") (pintype "input"))
    )
    (net (code "192") (name "Net-(E27C-I0)") (class "Default")
      (node (ref "E27") (pin "9") (pinfunction "I0_9") (pintype "input"))
      (node (ref "E8") (pin "3") (pinfunction "O_3") (pintype "output"))
    )
    (net (code "193") (name "Net-(E27C-O)") (class "Default")
      (node (ref "E27") (pin "8") (pinfunction "O_8") (pintype "output"))
      (node (ref "E45") (pin "2") (pinfunction "I0_2") (pintype "input"))
      (node (ref "E45") (pin "3") (pinfunction "I1_3") (pintype "input"))
    )
    (net (code "194") (name "Net-(E28A-I0)") (class "Default")
      (node (ref "E28") (pin "2") (pinfunction "I0_2") (pintype "input"))
      (node (ref "E28") (pin "3") (pinfunction "I1_3") (pintype "input"))
      (node (ref "E28") (pin "5") (pinfunction "I0_5") (pintype "input"))
      (node (ref "E28") (pin "6") (pinfunction "I1_6") (pintype "input"))
      (node (ref "E43") (pin "6") (pinfunction "O_6") (pintype "output"))
    )
    (net (code "195") (name "Net-(E28C-I0)") (class "Default")
      (node (ref "E28") (pin "8") (pinfunction "I0_8") (pintype "input"))
      (node (ref "E28") (pin "9") (pinfunction "I1_9") (pintype "input"))
      (node (ref "E8") (pin "8") (pinfunction "O_8") (pintype "output"))
    )
    (net (code "196") (name "Net-(E30A-CLR)") (class "Default")
      (node (ref "E30") (pin "1") (pinfunction "CLR_1") (pintype "input"))
      (node (ref "E34") (pin "11") (pinfunction "O_11") (pintype "output"))
    )
    (net (code "197") (name "Net-(E30B-CLR)") (class "Default")
      (node (ref "E30") (pin "13") (pinfunction "CLR_13") (pintype "input"))
      (node (ref "E34") (pin "6") (pinfunction "O_6") (pintype "output"))
    )
    (net (code "198") (name "Net-(E31A-I0)") (class "Default")
      (node (ref "E31") (pin "1") (pinfunction "I0_1") (pintype "input"))
      (node (ref "R7") (pin "1") (pinfunction "1_1") (pintype "passive"))
      (node (ref "W32") (pin "2") (pinfunction "2_2") (pintype "passive"))
    )
    (net (code "199") (name "Net-(E31A-O)") (class "Default")
      (node (ref "E31") (pin "3") (pinfunction "O_3") (pintype "output"))
      (node (ref "E43") (pin "12") (pinfunction "I0_12") (pintype "input"))
      (node (ref "E43") (pin "13") (pinfunction "I1_13") (pintype "input"))
    )
    (net (code "200") (name "Net-(E31B-I0)") (class "Default")
      (node (ref "E31") (pin "4") (pinfunction "I0_4") (pintype "input"))
      (node (ref "R8") (pin "1") (pinfunction "1_1") (pintype "passive"))
      (node (ref "W31") (pin "2") (pinfunction "2_2") (pintype "passive"))
    )
    (net (code "201") (name "Net-(E31B-O)") (class "Default")
      (node (ref "E31") (pin "6") (pinfunction "O_6") (pintype "output"))
      (node (ref "E43") (pin "10") (pinfunction "I1_10") (pintype "input"))
      (node (ref "E43") (pin "9") (pinfunction "I0_9") (pintype "input"))
    )
    (net (code "202") (name "Net-(E31C-I1)") (class "Default")
      (node (ref "E31") (pin "10") (pinfunction "I1_10") (pintype "input"))
      (node (ref "R12") (pin "1") (pinfunction "1_1") (pintype "passive"))
      (node (ref "W30") (pin "2") (pinfunction "2_2") (pintype "passive"))
    )
    (net (code "203") (name "Net-(E31D-I0)") (class "Default")
      (node (ref "E31") (pin "12") (pinfunction "I0_12") (pintype "input"))
      (node (ref "E4") (pin "8") (pinfunction "O_8") (pintype "output"))
    )
    (net (code "204") (name "Net-(E31D-I1)") (class "Default")
      (node (ref "E31") (pin "13") (pinfunction "I1_13") (pintype "input"))
      (node (ref "R11") (pin "1") (pinfunction "1_1") (pintype "passive"))
      (node (ref "W29") (pin "2") (pinfunction "2_2") (pintype "passive"))
    )
    (net (code "205") (name "Net-(E42A-I0)") (class "Default")
      (node (ref "E42") (pin "1") (pinfunction "I0_1") (pintype "input"))
      (node (ref "E42") (pin "2") (pinfunction "I1_2") (pintype "input"))
      (node (ref "E44") (pin "4") (pinfunction "~{Q}_4") (pintype "output"))
    )
    (net (code "206") (name "Net-(E42B-I0)") (class "Default")
      (node (ref "E42") (pin "4") (pinfunction "I0_4") (pintype "input"))
      (node (ref "E42") (pin "5") (pinfunction "I1_5") (pintype "input"))
      (node (ref "E44") (pin "5") (pinfunction "Q_5") (pintype "output"))
    )
    (net (code "207") (name "Net-(E42C-I0)") (class "Default")
      (node (ref "E42") (pin "10") (pinfunction "I1_10") (pintype "input"))
      (node (ref "E42") (pin "9") (pinfunction "I0_9") (pintype "input"))
      (node (ref "E44") (pin "13") (pinfunction "Q_13") (pintype "output"))
    )
    (net (code "208") (name "Net-(E42D-I0)") (class "Default")
      (node (ref "E42") (pin "12") (pinfunction "I0_12") (pintype "input"))
      (node (ref "E42") (pin "13") (pinfunction "I1_13") (pintype "input"))
      (node (ref "E44") (pin "12") (pinfunction "~{Q}_12") (pintype "output"))
    )
    (net (code "209") (name "Net-(E44A-C)") (class "Default")
      (node (ref "E44") (pin "14") (pinfunction "C_14") (pintype "input"))
      (node (ref "W27") (pin "2") (pinfunction "2_2") (pintype "passive"))
    )
    (net (code "210") (name "Net-(E44A-R{slash}C)") (class "Default")
      (node (ref "E44") (pin "15") (pinfunction "R/C_15") (pintype "input"))
      (node (ref "R21") (pin "2") (pinfunction "2_2") (pintype "passive"))
      (node (ref "W27") (pin "1") (pinfunction "1_1") (pintype "passive"))
    )
    (net (code "211") (name "Net-(E44B-C)") (class "Default")
      (node (ref "E44") (pin "6") (pinfunction "C_6") (pintype "input"))
      (node (ref "W25") (pin "2") (pinfunction "2_2") (pintype "passive"))
    )
    (net (code "212") (name "Net-(E44B-R{slash}C)") (class "Default")
      (node (ref "E44") (pin "7") (pinfunction "R/C_7") (pintype "input"))
      (node (ref "R22") (pin "2") (pinfunction "2_2") (pintype "passive"))
      (node (ref "W25") (pin "1") (pinfunction "1_1") (pintype "passive"))
    )
    (net (code "213") (name "Net-(R23-A)") (class "Default")
      (node (ref "R21") (pin "1") (pinfunction "1_1") (pintype "passive"))
      (node (ref "R23") (pin "1") (pinfunction "A_1") (pintype "passive"))
      (node (ref "W28") (pin "1") (pinfunction "1_1") (pintype "passive"))
    )
    (net (code "214") (name "Net-(R24-A)") (class "Default")
      (node (ref "R22") (pin "1") (pinfunction "1_1") (pintype "passive"))
      (node (ref "R24") (pin "1") (pinfunction "A_1") (pintype "passive"))
      (node (ref "W26") (pin "1") (pinfunction "1_1") (pintype "passive"))
    )
    (net (code "215") (name "TP3") (class "Default")
      (node (ref "E32") (pin "5") (pinfunction "Y3_5") (pintype "input"))
      (node (ref "U$2") (pin "CH2") (pinfunction "1_CH2") (pintype "bidirectional"))
    )
    (net (code "216") (name "TP3H") (class "Default")
      (node (ref "E16") (pin "10") (pinfunction "I1_10") (pintype "input"))
      (node (ref "E16") (pin "12") (pinfunction "I0_12") (pintype "input"))
      (node (ref "E18") (pin "10") (pinfunction "O_10") (pintype "output"))
    )
    (net (code "217") (name "TP3L") (class "Default")
      (node (ref "E18") (pin "11") (pinfunction "I_11") (pintype "input"))
      (node (ref "E32") (pin "6") (pinfunction "A3_6") (pintype "output"))
    )
    (net (code "218") (name "VCC") (class "Default")
      (node (ref "C1") (pin "1") (pinfunction "1_1") (pintype "passive"))
      (node (ref "C10") (pin "1") (pinfunction "1_1") (pintype "passive"))
      (node (ref "C100") (pin "+") (pinfunction "+_+") (pintype "passive"))
      (node (ref "C101") (pin "+") (pinfunction "+_+") (pintype "passive"))
      (node (ref "C102") (pin "+") (pinfunction "+_+") (pintype "passive"))
      (node (ref "C11") (pin "1") (pinfunction "1_1") (pintype "passive"))
      (node (ref "C12") (pin "1") (pinfunction "1_1") (pintype "passive"))
      (node (ref "C13") (pin "1") (pinfunction "1_1") (pintype "passive"))
      (node (ref "C14") (pin "1") (pinfunction "1_1") (pintype "passive"))
      (node (ref "C15") (pin "1") (pinfunction "1_1") (pintype "passive"))
      (node (ref "C16") (pin "1") (pinfunction "1_1") (pintype "passive"))
      (node (ref "C17") (pin "1") (pinfunction "1_1") (pintype "passive"))
      (node (ref "C18") (pin "1") (pinfunction "1_1") (pintype "passive"))
      (node (ref "C19") (pin "1") (pinfunction "1_1") (pintype "passive"))
      (node (ref "C2") (pin "1") (pinfunction "1_1") (pintype "passive"))
      (node (ref "C20") (pin "1") (pinfunction "1_1") (pintype "passive"))
      (node (ref "C21") (pin "1") (pinfunction "1_1") (pintype "passive"))
      (node (ref "C22") (pin "1") (pinfunction "1_1") (pintype "passive"))
      (node (ref "C23") (pin "1") (pinfunction "1_1") (pintype "passive"))
      (node (ref "C24") (pin "1") (pinfunction "1_1") (pintype "passive"))
      (node (ref "C25") (pin "1") (pinfunction "1_1") (pintype "passive"))
      (node (ref "C26") (pin "1") (pinfunction "1_1") (pintype "passive"))
      (node (ref "C27") (pin "1") (pinfunction "1_1") (pintype "passive"))
      (node (ref "C28") (pin "1") (pinfunction "1_1") (pintype "passive"))
      (node (ref "C29") (pin "1") (pinfunction "1_1") (pintype "passive"))
      (node (ref "C3") (pin "1") (pinfunction "1_1") (pintype "passive"))
      (node (ref "C30") (pin "1") (pinfunction "1_1") (pintype "passive"))
      (node (ref "C31") (pin "1") (pinfunction "1_1") (pintype "passive"))
      (node (ref "C32") (pin "1") (pinfunction "1_1") (pintype "passive"))
      (node (ref "C4") (pin "1") (pinfunction "1_1") (pintype "passive"))
      (node (ref "C5") (pin "1") (pinfunction "1_1") (pintype "passive"))
      (node (ref "C6") (pin "1") (pinfunction "1_1") (pintype "passive"))
      (node (ref "C7") (pin "1") (pinfunction "1_1") (pintype "passive"))
      (node (ref "C8") (pin "1") (pinfunction "1_1") (pintype "passive"))
      (node (ref "C9") (pin "1") (pinfunction "1_1") (pintype "passive"))
      (node (ref "R1") (pin "2") (pinfunction "2_2") (pintype "passive"))
      (node (ref "R10") (pin "2") (pinfunction "2_2") (pintype "passive"))
      (node (ref "R11") (pin "2") (pinfunction "2_2") (pintype "passive"))
      (node (ref "R12") (pin "2") (pinfunction "2_2") (pintype "passive"))
      (node (ref "R13") (pin "2") (pinfunction "2_2") (pintype "passive"))
      (node (ref "R15") (pin "2") (pinfunction "2_2") (pintype "passive"))
      (node (ref "R17") (pin "2") (pinfunction "2_2") (pintype "passive"))
      (node (ref "R19") (pin "2") (pinfunction "2_2") (pintype "passive"))
      (node (ref "R23") (pin "2") (pinfunction "S_2") (pintype "passive"))
      (node (ref "R23") (pin "3") (pinfunction "E_3") (pintype "passive"))
      (node (ref "R24") (pin "2") (pinfunction "S_2") (pintype "passive"))
      (node (ref "R24") (pin "3") (pinfunction "E_3") (pintype "passive"))
      (node (ref "R3") (pin "2") (pinfunction "2_2") (pintype "passive"))
      (node (ref "R5") (pin "2") (pinfunction "2_2") (pintype "passive"))
      (node (ref "R7") (pin "2") (pinfunction "2_2") (pintype "passive"))
      (node (ref "R8") (pin "2") (pinfunction "2_2") (pintype "passive"))
      (node (ref "R9") (pin "2") (pinfunction "2_2") (pintype "passive"))
      (node (ref "U$2") (pin "AA2") (pinfunction "1_AA2") (pintype "bidirectional"))
      (node (ref "U$2") (pin "BA2") (pinfunction "1_BA2") (pintype "bidirectional"))
      (node (ref "U$2") (pin "CA2") (pinfunction "1_CA2") (pintype "bidirectional"))
      (node (ref "W26") (pin "2") (pinfunction "2_2") (pintype "passive"))
      (node (ref "W28") (pin "2") (pinfunction "2_2") (pintype "passive"))
    )
    (net (code "219") (name "unconnected-(E29A-O8-Pad10)") (class "Default")
      (node (ref "E29") (pin "10") (pinfunction "O8_10") (pintype "output"))
    )
    (net (code "220") (name "unconnected-(E29A-O9-Pad11)") (class "Default")
      (node (ref "E29") (pin "11") (pinfunction "O9_11") (pintype "output"))
    )
    (net (code "221") (name "unconnected-(E30A-D-Pad2)") (class "Default")
      (node (ref "E30") (pin "2") (pinfunction "D_2") (pintype "input"))
    )
    (net (code "222") (name "unconnected-(E30A-~{Q}-Pad6)") (class "Default")
      (node (ref "E30") (pin "6") (pinfunction "~{Q}_6") (pintype "output"))
    )
    (net (code "223") (name "unconnected-(E30B-D-Pad12)") (class "Default")
      (node (ref "E30") (pin "12") (pinfunction "D_12") (pintype "input"))
    )
    (net (code "224") (name "unconnected-(E30B-~{Q}-Pad8)") (class "Default")
      (node (ref "E30") (pin "8") (pinfunction "~{Q}_8") (pintype "output"))
    )
    (net (code "225") (name "unconnected-(E33A-O8-Pad10)") (class "Default")
      (node (ref "E33") (pin "10") (pinfunction "O8_10") (pintype "output"))
    )
    (net (code "226") (name "unconnected-(E33A-O9-Pad11)") (class "Default")
      (node (ref "E33") (pin "11") (pinfunction "O9_11") (pintype "output"))
    )
    (net (code "227") (name "unconnected-(E35A-D-Pad2)") (class "Default")
      (node (ref "E35") (pin "2") (pinfunction "D_2") (pintype "input"))
    )
    (net (code "228") (name "unconnected-(E35A-~{Q}-Pad6)") (class "Default")
      (node (ref "E35") (pin "6") (pinfunction "~{Q}_6") (pintype "output"))
    )
    (net (code "229") (name "unconnected-(E35B-D-Pad12)") (class "Default")
      (node (ref "E35") (pin "12") (pinfunction "D_12") (pintype "input"))
    )
    (net (code "230") (name "unconnected-(E35B-~{Q}-Pad8)") (class "Default")
      (node (ref "E35") (pin "8") (pinfunction "~{Q}_8") (pintype "output"))
    )
    (net (code "231") (name "~{C0}") (class "Default")
      (node (ref "E28") (pin "4") (pinfunction "O_4") (pintype "open_collector"))
      (node (ref "U$2") (pin "CE1") (pinfunction "1_CE1") (pintype "bidirectional"))
    )
    (net (code "232") (name "~{C1}") (class "Default")
      (node (ref "E28") (pin "1") (pinfunction "O_1") (pintype "open_collector"))
      (node (ref "U$2") (pin "CH1") (pinfunction "1_CH1") (pintype "bidirectional"))
    )
    (net (code "233") (name "~{DATA0}") (class "Default")
      (node (ref "E5") (pin "12") (pinfunction "B1_12") (pintype "bidirectional"))
      (node (ref "E9") (pin "10") (pinfunction "O_10") (pintype "open_collector"))
      (node (ref "U$2") (pin "AR1") (pinfunction "1_AR1") (pintype "bidirectional"))
    )
    (net (code "234") (name "~{DATA1}") (class "Default")
      (node (ref "E5") (pin "15") (pinfunction "B0_15") (pintype "bidirectional"))
      (node (ref "E9") (pin "13") (pinfunction "O_13") (pintype "open_collector"))
      (node (ref "U$2") (pin "AS1") (pinfunction "1_AS1") (pintype "bidirectional"))
    )
    (net (code "235") (name "~{DATA2}") (class "Default")
      (node (ref "E5") (pin "4") (pinfunction "B3_4") (pintype "bidirectional"))
      (node (ref "E9") (pin "4") (pinfunction "O_4") (pintype "open_collector"))
      (node (ref "U$2") (pin "AU1") (pinfunction "1_AU1") (pintype "bidirectional"))
    )
    (net (code "236") (name "~{DATA3}") (class "Default")
      (node (ref "E5") (pin "1") (pinfunction "B2_1") (pintype "bidirectional"))
      (node (ref "E9") (pin "1") (pinfunction "O_1") (pintype "open_collector"))
      (node (ref "U$2") (pin "AV1") (pinfunction "1_AV1") (pintype "bidirectional"))
    )
    (net (code "237") (name "~{DATA4}") (class "Default")
      (node (ref "E19") (pin "12") (pinfunction "B1_12") (pintype "bidirectional"))
      (node (ref "E24") (pin "10") (pinfunction "O_10") (pintype "open_collector"))
      (node (ref "U$2") (pin "BR1") (pinfunction "1_BR1") (pintype "bidirectional"))
    )
    (net (code "238") (name "~{DATA5}") (class "Default")
      (node (ref "E19") (pin "15") (pinfunction "B0_15") (pintype "bidirectional"))
      (node (ref "E24") (pin "13") (pinfunction "O_13") (pintype "open_collector"))
      (node (ref "U$2") (pin "BS1") (pinfunction "1_BS1") (pintype "bidirectional"))
    )
    (net (code "239") (name "~{DATA6}") (class "Default")
      (node (ref "E19") (pin "4") (pinfunction "B3_4") (pintype "bidirectional"))
      (node (ref "E24") (pin "4") (pinfunction "O_4") (pintype "open_collector"))
      (node (ref "U$2") (pin "BU1") (pinfunction "1_BU1") (pintype "bidirectional"))
    )
    (net (code "240") (name "~{DATA7}") (class "Default")
      (node (ref "E19") (pin "1") (pinfunction "B2_1") (pintype "bidirectional"))
      (node (ref "E24") (pin "1") (pinfunction "O_1") (pintype "open_collector"))
      (node (ref "U$2") (pin "BV1") (pinfunction "1_BV1") (pintype "bidirectional"))
    )
    (net (code "241") (name "~{DATA8}") (class "Default")
      (node (ref "E36") (pin "12") (pinfunction "B1_12") (pintype "bidirectional"))
      (node (ref "E39") (pin "10") (pinfunction "O_10") (pintype "open_collector"))
      (node (ref "U$2") (pin "DR1") (pinfunction "1_DR1") (pintype "bidirectional"))
    )
    (net (code "242") (name "~{DATA9}") (class "Default")
      (node (ref "E36") (pin "15") (pinfunction "B0_15") (pintype "bidirectional"))
      (node (ref "E39") (pin "13") (pinfunction "O_13") (pintype "open_collector"))
      (node (ref "U$2") (pin "DS1") (pinfunction "1_DS1") (pintype "bidirectional"))
    )
    (net (code "243") (name "~{DATA10}") (class "Default")
      (node (ref "E36") (pin "4") (pinfunction "B3_4") (pintype "bidirectional"))
      (node (ref "E39") (pin "4") (pinfunction "O_4") (pintype "open_collector"))
      (node (ref "U$2") (pin "DU1") (pinfunction "1_DU1") (pintype "bidirectional"))
    )
    (net (code "244") (name "~{DATA11}") (class "Default")
      (node (ref "E36") (pin "1") (pinfunction "B2_1") (pintype "bidirectional"))
      (node (ref "E39") (pin "1") (pinfunction "O_1") (pintype "open_collector"))
      (node (ref "U$2") (pin "DV1") (pinfunction "1_DV1") (pintype "bidirectional"))
    )
    (net (code "245") (name "~{INTERNAL_IO}") (class "Default")
      (node (ref "E28") (pin "13") (pinfunction "O_13") (pintype "open_collector"))
      (node (ref "U$2") (pin "CL1") (pinfunction "1_CL1") (pintype "bidirectional"))
    )
    (net (code "246") (name "~{INT_RQST}") (class "Default")
      (node (ref "E45") (pin "1") (pinfunction "O_1") (pintype "open_collector"))
      (node (ref "U$2") (pin "CP1") (pinfunction "1_CP1") (pintype "bidirectional"))
    )
    (net (code "247") (name "~{IO_PAUSE}") (class "Default")
      (node (ref "E14") (pin "1") (pinfunction "Y1_1") (pintype "input"))
      (node (ref "U$2") (pin "CD1") (pinfunction "1_CD1") (pintype "bidirectional"))
    )
    (net (code "248") (name "~{MD03}") (class "Default")
      (node (ref "E14") (pin "11") (pinfunction "Y1_11") (pintype "input"))
      (node (ref "U$2") (pin "AP1") (pinfunction "1_AP1") (pintype "bidirectional"))
    )
    (net (code "249") (name "~{MD04}") (class "Default")
      (node (ref "E14") (pin "5") (pinfunction "Y3_5") (pintype "input"))
      (node (ref "U$2") (pin "BK1") (pinfunction "1_BK1") (pintype "bidirectional"))
    )
    (net (code "250") (name "~{MD05}") (class "Default")
      (node (ref "E14") (pin "3") (pinfunction "Y2_3") (pintype "input"))
      (node (ref "U$2") (pin "BL1") (pinfunction "1_BL1") (pintype "bidirectional"))
    )
    (net (code "251") (name "~{MD06}") (class "Default")
      (node (ref "E14") (pin "13") (pinfunction "Y2_13") (pintype "input"))
      (node (ref "U$2") (pin "BM1") (pinfunction "1_BM1") (pintype "bidirectional"))
    )
    (net (code "252") (name "~{MD07}") (class "Default")
      (node (ref "E14") (pin "15") (pinfunction "Y3_15") (pintype "input"))
      (node (ref "U$2") (pin "BP1") (pinfunction "1_BP1") (pintype "bidirectional"))
    )
    (net (code "253") (name "~{MD08}") (class "Default")
      (node (ref "E32") (pin "1") (pinfunction "Y1_1") (pintype "input"))
      (node (ref "U$2") (pin "DK1") (pinfunction "1_DK1") (pintype "bidirectional"))
    )
    (net (code "254") (name "~{MD09}") (class "Default")
      (node (ref "E32") (pin "15") (pinfunction "Y3_15") (pintype "input"))
      (node (ref "U$2") (pin "DL1") (pinfunction "1_DL1") (pintype "bidirectional"))
    )
    (net (code "255") (name "~{MD10}") (class "Default")
      (node (ref "E32") (pin "13") (pinfunction "Y2_13") (pintype "input"))
      (node (ref "U$2") (pin "DM1") (pinfunction "1_DM1") (pintype "bidirectional"))
    )
    (net (code "256") (name "~{MD11}") (class "Default")
      (node (ref "E32") (pin "11") (pinfunction "Y1_11") (pintype "input"))
      (node (ref "U$2") (pin "DP1") (pinfunction "1_DP1") (pintype "bidirectional"))
    )
    (net (code "257") (name "~{SKIP}") (class "Default")
      (node (ref "E28") (pin "10") (pinfunction "O_10") (pintype "open_collector"))
      (node (ref "U$2") (pin "CS1") (pinfunction "1_CS1") (pintype "bidirectional"))
    )
  )
)
